# PS3604LR.net
KiCad netlist of a schematic drawn in Altium Designer
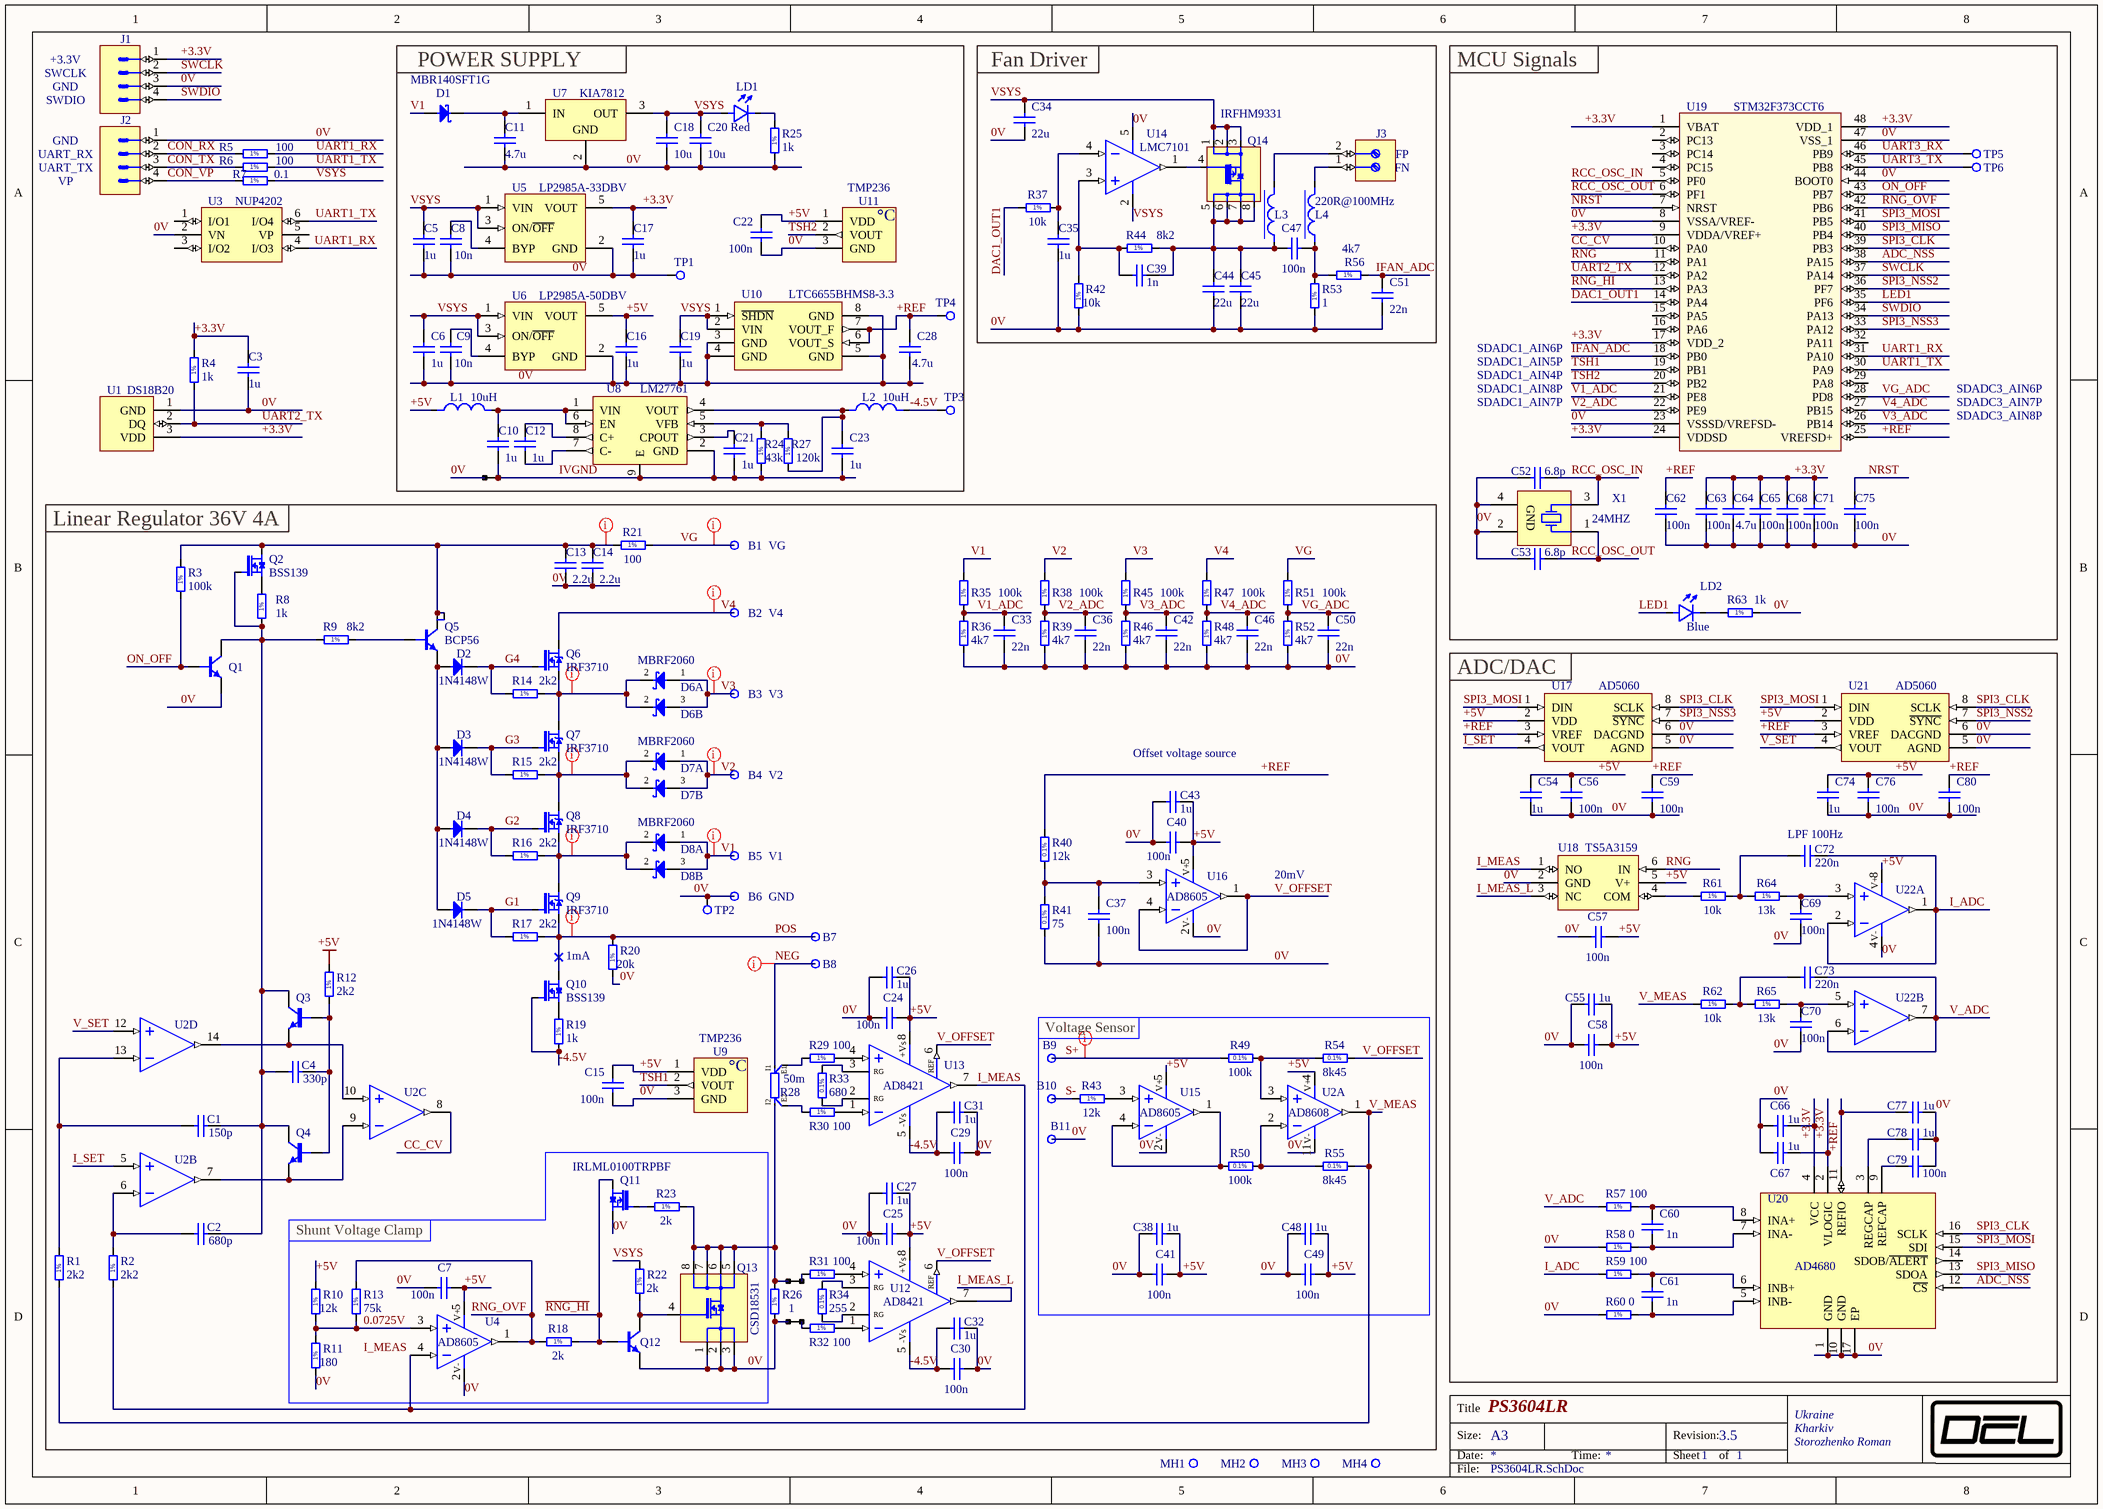
[diagram p0: PS3604LR.SchDoc]

(export (version "E")
  (design (tool "Eeschema 10.0.6"))
  (components
    (comp (ref "B1")
      (value "VG")
      (footprint "c250h130")
      (description "Single Terminal Socket")
      (fields (field (name "PART NUMBER") "PLATED_HOLE1.3_PAD2.5") (field (name "AUTHOR") "DEL"))
      (libsource (lib "Eletro-mechanical") (part "Single Terminal Socket"))
    )
    (comp (ref "B2")
      (value "V4")
      (footprint "c250h130")
      (description "Single Terminal Socket")
      (fields (field (name "PART NUMBER") "PLATED_HOLE1.3_PAD2.5") (field (name "AUTHOR") "DEL"))
      (libsource (lib "Eletro-mechanical") (part "Single Terminal Socket"))
    )
    (comp (ref "B3")
      (value "V3")
      (footprint "c250h130")
      (description "Single Terminal Socket")
      (fields (field (name "PART NUMBER") "PLATED_HOLE1.3_PAD2.5") (field (name "AUTHOR") "DEL"))
      (libsource (lib "Eletro-mechanical") (part "Single Terminal Socket"))
    )
    (comp (ref "B4")
      (value "V2")
      (footprint "c250h130")
      (description "Single Terminal Socket")
      (fields (field (name "PART NUMBER") "PLATED_HOLE1.3_PAD2.5") (field (name "AUTHOR") "DEL"))
      (libsource (lib "Eletro-mechanical") (part "Single Terminal Socket"))
    )
    (comp (ref "B5")
      (value "V1")
      (footprint "c250h130")
      (description "Single Terminal Socket")
      (fields (field (name "PART NUMBER") "PLATED_HOLE1.3_PAD2.5") (field (name "AUTHOR") "DEL"))
      (libsource (lib "Eletro-mechanical") (part "Single Terminal Socket"))
    )
    (comp (ref "B6")
      (value "GND")
      (footprint "c250h130")
      (description "Single Terminal Socket")
      (fields (field (name "PART NUMBER") "PLATED_HOLE1.3_PAD2.5") (field (name "AUTHOR") "DEL"))
      (libsource (lib "Eletro-mechanical") (part "Single Terminal Socket"))
    )
    (comp (ref "B7")
      (value "P")
      (footprint "c320h180")
      (description "Single Terminal Socket")
      (fields (field (name "PART NUMBER") "PLATED_HOLE1.8_PAD3.2") (field (name "AUTHOR") "DEL"))
      (libsource (lib "Eletro-mechanical") (part "Single Terminal Socket"))
    )
    (comp (ref "B8")
      (value "N")
      (footprint "c320h180")
      (description "Single Terminal Socket")
      (fields (field (name "PART NUMBER") "PLATED_HOLE1.8_PAD3.2") (field (name "AUTHOR") "DEL"))
      (libsource (lib "Eletro-mechanical") (part "Single Terminal Socket"))
    )
    (comp (ref "B9")
      (value "Plated Hole")
      (footprint "c150h100")
      (description "Single Terminal Socket")
      (fields (field (name "PART NUMBER") "PLATED_HOLE1.0_PAD1.5") (field (name "AUTHOR") "CERN DEM JLC"))
      (libsource (lib "Eletro-mechanical") (part "Single Terminal Socket"))
    )
    (comp (ref "B10")
      (value "Plated Hole")
      (footprint "c150h100")
      (description "Single Terminal Socket")
      (fields (field (name "PART NUMBER") "PLATED_HOLE1.0_PAD1.5") (field (name "AUTHOR") "CERN DEM JLC"))
      (libsource (lib "Eletro-mechanical") (part "Single Terminal Socket"))
    )
    (comp (ref "B11")
      (value "Plated Hole")
      (footprint "c150h100")
      (description "Single Terminal Socket")
      (fields (field (name "PART NUMBER") "PLATED_HOLE1.0_PAD1.5") (field (name "AUTHOR") "CERN DEM JLC"))
      (libsource (lib "Eletro-mechanical") (part "Single Terminal Socket"))
    )
    (comp (ref "C1")
      (value "150p")
      (footprint "CAPC2012X135N")
      (description "Non-polarised capacitor")
      (fields
        (field (name "PART NUMBER") "CC0805_150PF_50V_5%_NP0")
        (field (name "VOLTAGE") "50V")
        (field (name "AUTHOR") "CERN DEM JLC")
      )
      (libsource (lib "Capacitors") (part "Capacitor - non polarized"))
    )
    (comp (ref "C2")
      (value "680p")
      (footprint "CAPC2012X135N")
      (description "Non-polarised capacitor")
      (fields
        (field (name "PART NUMBER") "CC0805_680PF_50V_5%_NP0")
        (field (name "VOLTAGE") "50V")
        (field (name "AUTHOR") "CERN DEM JLC")
      )
      (libsource (lib "Capacitors") (part "Capacitor - non polarized"))
    )
    (comp (ref "C3")
      (value "1u")
      (footprint "CAPC1005X55N")
      (description "Non-polarised capacitor")
      (fields
        (field (name "PART NUMBER") "CC0402_1UF_10V_20%_X5R")
        (field (name "VOLTAGE") "10V")
        (field (name "AUTHOR") "ELMAN")
      )
      (libsource (lib "Capacitors") (part "Capacitor - non polarized"))
    )
    (comp (ref "C4")
      (value "330p")
      (footprint "CAPC2012X135N")
      (description "Non-polarised capacitor")
      (fields
        (field (name "PART NUMBER") "CC0805_330PF_50V_5%_NP0")
        (field (name "VOLTAGE") "50V")
        (field (name "AUTHOR") "CERN DEM JLC")
      )
      (libsource (lib "Capacitors") (part "Capacitor - non polarized"))
    )
    (comp (ref "C5")
      (value "1u")
      (footprint "CAPC1005X55N")
      (description "Non-polarised capacitor")
      (fields
        (field (name "PART NUMBER") "CC0402_1UF_10V_20%_X5R")
        (field (name "VOLTAGE") "10V")
        (field (name "AUTHOR") "ELMAN")
      )
      (libsource (lib "Capacitors") (part "Capacitor - non polarized"))
    )
    (comp (ref "C6")
      (value "1u")
      (footprint "CAPC1005X55N")
      (description "Non-polarised capacitor")
      (fields
        (field (name "PART NUMBER") "CC0402_1UF_10V_20%_X5R")
        (field (name "VOLTAGE") "10V")
        (field (name "AUTHOR") "ELMAN")
      )
      (libsource (lib "Capacitors") (part "Capacitor - non polarized"))
    )
    (comp (ref "C7")
      (value "100n")
      (footprint "CAPC1005X55N")
      (description "Non-polarised capacitor")
      (fields
        (field (name "PART NUMBER") "CC0402_100NF_50V_10%_X7R")
        (field (name "VOLTAGE") "50V")
        (field (name "AUTHOR") "DEL")
      )
      (libsource (lib "Capacitors") (part "Capacitor - non polarized"))
    )
    (comp (ref "C8")
      (value "10n")
      (footprint "CAPC1005X55N")
      (description "Non-polarised capacitor")
      (fields
        (field (name "PART NUMBER") "CC0402_10NF_50V_10%_X7R")
        (field (name "VOLTAGE") "50V")
        (field (name "AUTHOR") "DEL")
      )
      (libsource (lib "Capacitors") (part "Capacitor - non polarized"))
    )
    (comp (ref "C9")
      (value "10n")
      (footprint "CAPC1005X55N")
      (description "Non-polarised capacitor")
      (fields
        (field (name "PART NUMBER") "CC0402_10NF_50V_10%_X7R")
        (field (name "VOLTAGE") "50V")
        (field (name "AUTHOR") "DEL")
      )
      (libsource (lib "Capacitors") (part "Capacitor - non polarized"))
    )
    (comp (ref "C10")
      (value "1u")
      (footprint "CAPC1005X55N")
      (description "Non-polarised capacitor")
      (fields
        (field (name "PART NUMBER") "CC0402_1UF_10V_20%_X5R")
        (field (name "VOLTAGE") "10V")
        (field (name "AUTHOR") "ELMAN")
      )
      (libsource (lib "Capacitors") (part "Capacitor - non polarized"))
    )
    (comp (ref "C11")
      (value "4.7u")
      (footprint "CAPC3216X140N")
      (description "Non-polarised capacitor")
      (fields
        (field (name "PART NUMBER") "CC1206_4.7UF_50V_10%_X7R")
        (field (name "VOLTAGE") "50V")
        (field (name "AUTHOR") "DEL")
      )
      (libsource (lib "Capacitors") (part "Capacitor - non polarized"))
    )
    (comp (ref "C12")
      (value "1u")
      (footprint "CAPC1005X55N")
      (description "Non-polarised capacitor")
      (fields
        (field (name "PART NUMBER") "CC0402_1UF_10V_20%_X5R")
        (field (name "VOLTAGE") "10V")
        (field (name "AUTHOR") "ELMAN")
      )
      (libsource (lib "Capacitors") (part "Capacitor - non polarized"))
    )
    (comp (ref "C13")
      (value "2.2u")
      (footprint "CAPC3216X140N")
      (description "Non-polarised capacitor")
      (fields
        (field (name "PART NUMBER") "CC1206_2.2UF_100V_10%_X7R")
        (field (name "VOLTAGE") "100V")
        (field (name "AUTHOR") "DEL")
      )
      (libsource (lib "Capacitors") (part "Capacitor - non polarized"))
    )
    (comp (ref "C14")
      (value "2.2u")
      (footprint "CAPC3216X140N")
      (description "Non-polarised capacitor")
      (fields
        (field (name "PART NUMBER") "CC1206_2.2UF_100V_10%_X7R")
        (field (name "VOLTAGE") "100V")
        (field (name "AUTHOR") "DEL")
      )
      (libsource (lib "Capacitors") (part "Capacitor - non polarized"))
    )
    (comp (ref "C15")
      (value "100n")
      (footprint "CAPC1005X55N")
      (description "Non-polarised capacitor")
      (fields
        (field (name "PART NUMBER") "CC0402_100NF_50V_10%_X7R")
        (field (name "VOLTAGE") "50V")
        (field (name "AUTHOR") "DEL")
      )
      (libsource (lib "Capacitors") (part "Capacitor - non polarized"))
    )
    (comp (ref "C16")
      (value "1u")
      (footprint "CAPC1005X55N")
      (description "Non-polarised capacitor")
      (fields
        (field (name "PART NUMBER") "CC0402_1UF_10V_20%_X5R")
        (field (name "VOLTAGE") "10V")
        (field (name "AUTHOR") "ELMAN")
      )
      (libsource (lib "Capacitors") (part "Capacitor - non polarized"))
    )
    (comp (ref "C17")
      (value "1u")
      (footprint "CAPC1005X55N")
      (description "Non-polarised capacitor")
      (fields
        (field (name "PART NUMBER") "CC0402_1UF_10V_20%_X5R")
        (field (name "VOLTAGE") "10V")
        (field (name "AUTHOR") "ELMAN")
      )
      (libsource (lib "Capacitors") (part "Capacitor - non polarized"))
    )
    (comp (ref "C18")
      (value "10u")
      (footprint "CAPC3216X140N")
      (description "Non-polarised capacitor")
      (fields
        (field (name "PART NUMBER") "CC1206_10UF_16V_10%_X7R")
        (field (name "VOLTAGE") "16V")
        (field (name "AUTHOR") "CERN DEM JLC")
      )
      (libsource (lib "Capacitors") (part "Capacitor - non polarized"))
    )
    (comp (ref "C19")
      (value "1u")
      (footprint "CAPC1005X55N")
      (description "Non-polarised capacitor")
      (fields
        (field (name "PART NUMBER") "CC0402_1UF_10V_20%_X5R")
        (field (name "VOLTAGE") "10V")
        (field (name "AUTHOR") "ELMAN")
      )
      (libsource (lib "Capacitors") (part "Capacitor - non polarized"))
    )
    (comp (ref "C20")
      (value "10u")
      (footprint "CAPC3216X140N")
      (description "Non-polarised capacitor")
      (fields
        (field (name "PART NUMBER") "CC1206_10UF_16V_10%_X7R")
        (field (name "VOLTAGE") "16V")
        (field (name "AUTHOR") "CERN DEM JLC")
      )
      (libsource (lib "Capacitors") (part "Capacitor - non polarized"))
    )
    (comp (ref "C21")
      (value "1u")
      (footprint "CAPC1005X55N")
      (description "Non-polarised capacitor")
      (fields
        (field (name "PART NUMBER") "CC0402_1UF_10V_20%_X5R")
        (field (name "VOLTAGE") "10V")
        (field (name "AUTHOR") "ELMAN")
      )
      (libsource (lib "Capacitors") (part "Capacitor - non polarized"))
    )
    (comp (ref "C22")
      (value "100n")
      (footprint "CAPC1005X55N")
      (description "Non-polarised capacitor")
      (fields
        (field (name "PART NUMBER") "CC0402_100NF_50V_10%_X7R")
        (field (name "VOLTAGE") "50V")
        (field (name "AUTHOR") "DEL")
      )
      (libsource (lib "Capacitors") (part "Capacitor - non polarized"))
    )
    (comp (ref "C23")
      (value "1u")
      (footprint "CAPC1005X55N")
      (description "Non-polarised capacitor")
      (fields
        (field (name "PART NUMBER") "CC0402_1UF_10V_20%_X5R")
        (field (name "VOLTAGE") "10V")
        (field (name "AUTHOR") "ELMAN")
      )
      (libsource (lib "Capacitors") (part "Capacitor - non polarized"))
    )
    (comp (ref "C24")
      (value "100n")
      (footprint "CAPC1005X55N")
      (description "Non-polarised capacitor")
      (fields
        (field (name "PART NUMBER") "CC0402_100NF_50V_10%_X7R")
        (field (name "VOLTAGE") "50V")
        (field (name "AUTHOR") "DEL")
      )
      (libsource (lib "Capacitors") (part "Capacitor - non polarized"))
    )
    (comp (ref "C25")
      (value "100n")
      (footprint "CAPC1005X55N")
      (description "Non-polarised capacitor")
      (fields
        (field (name "PART NUMBER") "CC0402_100NF_50V_10%_X7R")
        (field (name "VOLTAGE") "50V")
        (field (name "AUTHOR") "DEL")
      )
      (libsource (lib "Capacitors") (part "Capacitor - non polarized"))
    )
    (comp (ref "C26")
      (value "1u")
      (footprint "CAPC1005X55N")
      (description "Non-polarised capacitor")
      (fields
        (field (name "PART NUMBER") "CC0402_1UF_10V_20%_X5R")
        (field (name "VOLTAGE") "10V")
        (field (name "AUTHOR") "ELMAN")
      )
      (libsource (lib "Capacitors") (part "Capacitor - non polarized"))
    )
    (comp (ref "C27")
      (value "1u")
      (footprint "CAPC1005X55N")
      (description "Non-polarised capacitor")
      (fields
        (field (name "PART NUMBER") "CC0402_1UF_10V_20%_X5R")
        (field (name "VOLTAGE") "10V")
        (field (name "AUTHOR") "ELMAN")
      )
      (libsource (lib "Capacitors") (part "Capacitor - non polarized"))
    )
    (comp (ref "C28")
      (value "4.7u")
      (footprint "CAPC1005X55N")
      (description "Non-polarised capacitor")
      (fields
        (field (name "PART NUMBER") "CC0402_4.7UF_10V_20%_X5R")
        (field (name "VOLTAGE") "10V")
        (field (name "AUTHOR") "DEL")
      )
      (libsource (lib "Capacitors") (part "Capacitor - non polarized"))
    )
    (comp (ref "C29")
      (value "100n")
      (footprint "CAPC1005X55N")
      (description "Non-polarised capacitor")
      (fields
        (field (name "PART NUMBER") "CC0402_100NF_50V_10%_X7R")
        (field (name "VOLTAGE") "50V")
        (field (name "AUTHOR") "DEL")
      )
      (libsource (lib "Capacitors") (part "Capacitor - non polarized"))
    )
    (comp (ref "C30")
      (value "100n")
      (footprint "CAPC1005X55N")
      (description "Non-polarised capacitor")
      (fields
        (field (name "PART NUMBER") "CC0402_100NF_50V_10%_X7R")
        (field (name "VOLTAGE") "50V")
        (field (name "AUTHOR") "DEL")
      )
      (libsource (lib "Capacitors") (part "Capacitor - non polarized"))
    )
    (comp (ref "C31")
      (value "1u")
      (footprint "CAPC1005X55N")
      (description "Non-polarised capacitor")
      (fields
        (field (name "PART NUMBER") "CC0402_1UF_10V_20%_X5R")
        (field (name "VOLTAGE") "10V")
        (field (name "AUTHOR") "ELMAN")
      )
      (libsource (lib "Capacitors") (part "Capacitor - non polarized"))
    )
    (comp (ref "C32")
      (value "1u")
      (footprint "CAPC1005X55N")
      (description "Non-polarised capacitor")
      (fields
        (field (name "PART NUMBER") "CC0402_1UF_10V_20%_X5R")
        (field (name "VOLTAGE") "10V")
        (field (name "AUTHOR") "ELMAN")
      )
      (libsource (lib "Capacitors") (part "Capacitor - non polarized"))
    )
    (comp (ref "C33")
      (value "22n")
      (footprint "CAPC1005X55N")
      (description "Non-polarised capacitor")
      (fields
        (field (name "PART NUMBER") "CC0402_22NF_16V_10%_X7R")
        (field (name "VOLTAGE") "16V")
        (field (name "AUTHOR") "CERN DEM JLC")
      )
      (libsource (lib "Capacitors") (part "Capacitor - non polarized"))
    )
    (comp (ref "C34")
      (value "22u")
      (footprint "CAPC3216X100N")
      (description "Non-polarised capacitor")
      (fields
        (field (name "PART NUMBER") "CC1206_22UF_16V_20%_X5R")
        (field (name "VOLTAGE") "16V")
        (field (name "AUTHOR") "D_EL")
      )
      (libsource (lib "Capacitors") (part "Capacitor - non polarized"))
    )
    (comp (ref "C35")
      (value "1u")
      (footprint "CAPC1005X55N")
      (description "Non-polarised capacitor")
      (fields
        (field (name "PART NUMBER") "CC0402_1UF_10V_20%_X5R")
        (field (name "VOLTAGE") "10V")
        (field (name "AUTHOR") "ELMAN")
      )
      (libsource (lib "Capacitors") (part "Capacitor - non polarized"))
    )
    (comp (ref "C36")
      (value "22n")
      (footprint "CAPC1005X55N")
      (description "Non-polarised capacitor")
      (fields
        (field (name "PART NUMBER") "CC0402_22NF_16V_10%_X7R")
        (field (name "VOLTAGE") "16V")
        (field (name "AUTHOR") "CERN DEM JLC")
      )
      (libsource (lib "Capacitors") (part "Capacitor - non polarized"))
    )
    (comp (ref "C37")
      (value "100n")
      (footprint "CAPC1005X55N")
      (description "Non-polarised capacitor")
      (fields
        (field (name "PART NUMBER") "CC0402_100NF_50V_10%_X7R")
        (field (name "VOLTAGE") "50V")
        (field (name "AUTHOR") "DEL")
      )
      (libsource (lib "Capacitors") (part "Capacitor - non polarized"))
    )
    (comp (ref "C38")
      (value "1u")
      (footprint "CAPC1005X55N")
      (description "Non-polarised capacitor")
      (fields
        (field (name "PART NUMBER") "CC0402_1UF_10V_20%_X5R")
        (field (name "VOLTAGE") "10V")
        (field (name "AUTHOR") "ELMAN")
      )
      (libsource (lib "Capacitors") (part "Capacitor - non polarized"))
    )
    (comp (ref "C39")
      (value "1n")
      (footprint "CAPC1005X55N")
      (description "Non-polarised capacitor")
      (fields
        (field (name "PART NUMBER") "CC0402_1NF_50V_5%_NP0")
        (field (name "VOLTAGE") "50V")
        (field (name "AUTHOR") "ROMAN")
      )
      (libsource (lib "Capacitors") (part "Capacitor - non polarized"))
    )
    (comp (ref "C40")
      (value "100n")
      (footprint "CAPC1005X55N")
      (description "Non-polarised capacitor")
      (fields
        (field (name "PART NUMBER") "CC0402_100NF_50V_10%_X7R")
        (field (name "VOLTAGE") "50V")
        (field (name "AUTHOR") "DEL")
      )
      (libsource (lib "Capacitors") (part "Capacitor - non polarized"))
    )
    (comp (ref "C41")
      (value "100n")
      (footprint "CAPC1005X55N")
      (description "Non-polarised capacitor")
      (fields
        (field (name "PART NUMBER") "CC0402_100NF_50V_10%_X7R")
        (field (name "VOLTAGE") "50V")
        (field (name "AUTHOR") "DEL")
      )
      (libsource (lib "Capacitors") (part "Capacitor - non polarized"))
    )
    (comp (ref "C42")
      (value "22n")
      (footprint "CAPC1005X55N")
      (description "Non-polarised capacitor")
      (fields
        (field (name "PART NUMBER") "CC0402_22NF_16V_10%_X7R")
        (field (name "VOLTAGE") "16V")
        (field (name "AUTHOR") "CERN DEM JLC")
      )
      (libsource (lib "Capacitors") (part "Capacitor - non polarized"))
    )
    (comp (ref "C43")
      (value "1u")
      (footprint "CAPC1005X55N")
      (description "Non-polarised capacitor")
      (fields
        (field (name "PART NUMBER") "CC0402_1UF_10V_20%_X5R")
        (field (name "VOLTAGE") "10V")
        (field (name "AUTHOR") "ELMAN")
      )
      (libsource (lib "Capacitors") (part "Capacitor - non polarized"))
    )
    (comp (ref "C44")
      (value "22u")
      (footprint "CAPC3216X100N")
      (description "Non-polarised capacitor")
      (fields
        (field (name "PART NUMBER") "CC1206_22UF_16V_20%_X5R")
        (field (name "VOLTAGE") "16V")
        (field (name "AUTHOR") "D_EL")
      )
      (libsource (lib "Capacitors") (part "Capacitor - non polarized"))
    )
    (comp (ref "C45")
      (value "22u")
      (footprint "CAPC3216X100N")
      (description "Non-polarised capacitor")
      (fields
        (field (name "PART NUMBER") "CC1206_22UF_16V_20%_X5R")
        (field (name "VOLTAGE") "16V")
        (field (name "AUTHOR") "D_EL")
      )
      (libsource (lib "Capacitors") (part "Capacitor - non polarized"))
    )
    (comp (ref "C46")
      (value "22n")
      (footprint "CAPC1005X55N")
      (description "Non-polarised capacitor")
      (fields
        (field (name "PART NUMBER") "CC0402_22NF_16V_10%_X7R")
        (field (name "VOLTAGE") "16V")
        (field (name "AUTHOR") "CERN DEM JLC")
      )
      (libsource (lib "Capacitors") (part "Capacitor - non polarized"))
    )
    (comp (ref "C47")
      (value "100n")
      (footprint "CAPC1005X55N")
      (description "Non-polarised capacitor")
      (fields
        (field (name "PART NUMBER") "CC0402_100NF_50V_10%_X7R")
        (field (name "VOLTAGE") "50V")
        (field (name "AUTHOR") "DEL")
      )
      (libsource (lib "Capacitors") (part "Capacitor - non polarized"))
    )
    (comp (ref "C48")
      (value "1u")
      (footprint "CAPC1005X55N")
      (description "Non-polarised capacitor")
      (fields
        (field (name "PART NUMBER") "CC0402_1UF_10V_20%_X5R")
        (field (name "VOLTAGE") "10V")
        (field (name "AUTHOR") "ELMAN")
      )
      (libsource (lib "Capacitors") (part "Capacitor - non polarized"))
    )
    (comp (ref "C49")
      (value "100n")
      (footprint "CAPC1005X55N")
      (description "Non-polarised capacitor")
      (fields
        (field (name "PART NUMBER") "CC0402_100NF_50V_10%_X7R")
        (field (name "VOLTAGE") "50V")
        (field (name "AUTHOR") "DEL")
      )
      (libsource (lib "Capacitors") (part "Capacitor - non polarized"))
    )
    (comp (ref "C50")
      (value "22n")
      (footprint "CAPC1005X55N")
      (description "Non-polarised capacitor")
      (fields
        (field (name "PART NUMBER") "CC0402_22NF_16V_10%_X7R")
        (field (name "VOLTAGE") "16V")
        (field (name "AUTHOR") "CERN DEM JLC")
      )
      (libsource (lib "Capacitors") (part "Capacitor - non polarized"))
    )
    (comp (ref "C51")
      (value "22n")
      (footprint "CAPC1005X55N")
      (description "Non-polarised capacitor")
      (fields
        (field (name "PART NUMBER") "CC0402_22NF_16V_10%_X7R")
        (field (name "VOLTAGE") "16V")
        (field (name "AUTHOR") "CERN DEM JLC")
      )
      (libsource (lib "Capacitors") (part "Capacitor - non polarized"))
    )
    (comp (ref "C52")
      (value "6.8p")
      (footprint "CAPC1005X55N")
      (description "Non-polarised capacitor")
      (fields
        (field (name "PART NUMBER") "CC0402_6.8PF_50V_0.5PF_NP0")
        (field (name "VOLTAGE") "50V")
        (field (name "AUTHOR") "CERN DEM JLC")
      )
      (libsource (lib "Capacitors") (part "Capacitor - non polarized"))
    )
    (comp (ref "C53")
      (value "6.8p")
      (footprint "CAPC1005X55N")
      (description "Non-polarised capacitor")
      (fields
        (field (name "PART NUMBER") "CC0402_6.8PF_50V_0.5PF_NP0")
        (field (name "VOLTAGE") "50V")
        (field (name "AUTHOR") "CERN DEM JLC")
      )
      (libsource (lib "Capacitors") (part "Capacitor - non polarized"))
    )
    (comp (ref "C54")
      (value "1u")
      (footprint "CAPC1005X55N")
      (description "Non-polarised capacitor")
      (fields
        (field (name "PART NUMBER") "CC0402_1UF_10V_20%_X5R")
        (field (name "VOLTAGE") "10V")
        (field (name "AUTHOR") "ELMAN")
      )
      (libsource (lib "Capacitors") (part "Capacitor - non polarized"))
    )
    (comp (ref "C55")
      (value "1u")
      (footprint "CAPC1005X55N")
      (description "Non-polarised capacitor")
      (fields
        (field (name "PART NUMBER") "CC0402_1UF_10V_20%_X5R")
        (field (name "VOLTAGE") "10V")
        (field (name "AUTHOR") "ELMAN")
      )
      (libsource (lib "Capacitors") (part "Capacitor - non polarized"))
    )
    (comp (ref "C56")
      (value "100n")
      (footprint "CAPC1005X55N")
      (description "Non-polarised capacitor")
      (fields
        (field (name "PART NUMBER") "CC0402_100NF_50V_10%_X7R")
        (field (name "VOLTAGE") "50V")
        (field (name "AUTHOR") "DEL")
      )
      (libsource (lib "Capacitors") (part "Capacitor - non polarized"))
    )
    (comp (ref "C57")
      (value "100n")
      (footprint "CAPC1005X55N")
      (description "Non-polarised capacitor")
      (fields
        (field (name "PART NUMBER") "CC0402_100NF_50V_10%_X7R")
        (field (name "VOLTAGE") "50V")
        (field (name "AUTHOR") "DEL")
      )
      (libsource (lib "Capacitors") (part "Capacitor - non polarized"))
    )
    (comp (ref "C58")
      (value "100n")
      (footprint "CAPC1005X55N")
      (description "Non-polarised capacitor")
      (fields
        (field (name "PART NUMBER") "CC0402_100NF_50V_10%_X7R")
        (field (name "VOLTAGE") "50V")
        (field (name "AUTHOR") "DEL")
      )
      (libsource (lib "Capacitors") (part "Capacitor - non polarized"))
    )
    (comp (ref "C59")
      (value "100n")
      (footprint "CAPC1005X55N")
      (description "Non-polarised capacitor")
      (fields
        (field (name "PART NUMBER") "CC0402_100NF_50V_10%_X7R")
        (field (name "VOLTAGE") "50V")
        (field (name "AUTHOR") "DEL")
      )
      (libsource (lib "Capacitors") (part "Capacitor - non polarized"))
    )
    (comp (ref "C60")
      (value "1n")
      (footprint "CAPC1005X55N")
      (description "Non-polarised capacitor")
      (fields
        (field (name "PART NUMBER") "CC0402_1NF_50V_5%_NP0")
        (field (name "VOLTAGE") "50V")
        (field (name "AUTHOR") "ROMAN")
      )
      (libsource (lib "Capacitors") (part "Capacitor - non polarized"))
    )
    (comp (ref "C61")
      (value "1n")
      (footprint "CAPC1005X55N")
      (description "Non-polarised capacitor")
      (fields
        (field (name "PART NUMBER") "CC0402_1NF_50V_5%_NP0")
        (field (name "VOLTAGE") "50V")
        (field (name "AUTHOR") "ROMAN")
      )
      (libsource (lib "Capacitors") (part "Capacitor - non polarized"))
    )
    (comp (ref "C62")
      (value "100n")
      (footprint "CAPC1005X55N")
      (description "Non-polarised capacitor")
      (fields
        (field (name "PART NUMBER") "CC0402_100NF_50V_10%_X7R")
        (field (name "VOLTAGE") "50V")
        (field (name "AUTHOR") "DEL")
      )
      (libsource (lib "Capacitors") (part "Capacitor - non polarized"))
    )
    (comp (ref "C63")
      (value "100n")
      (footprint "CAPC1005X55N")
      (description "Non-polarised capacitor")
      (fields
        (field (name "PART NUMBER") "CC0402_100NF_50V_10%_X7R")
        (field (name "VOLTAGE") "50V")
        (field (name "AUTHOR") "DEL")
      )
      (libsource (lib "Capacitors") (part "Capacitor - non polarized"))
    )
    (comp (ref "C64")
      (value "4.7u")
      (footprint "CAPC1005X55N")
      (description "Non-polarised capacitor")
      (fields
        (field (name "PART NUMBER") "CC0402_4.7UF_10V_20%_X5R")
        (field (name "VOLTAGE") "10V")
        (field (name "AUTHOR") "DEL")
      )
      (libsource (lib "Capacitors") (part "Capacitor - non polarized"))
    )
    (comp (ref "C65")
      (value "100n")
      (footprint "CAPC1005X55N")
      (description "Non-polarised capacitor")
      (fields
        (field (name "PART NUMBER") "CC0402_100NF_50V_10%_X7R")
        (field (name "VOLTAGE") "50V")
        (field (name "AUTHOR") "DEL")
      )
      (libsource (lib "Capacitors") (part "Capacitor - non polarized"))
    )
    (comp (ref "C66")
      (value "1u")
      (footprint "CAPC1005X55N")
      (description "Non-polarised capacitor")
      (fields
        (field (name "PART NUMBER") "CC0402_1UF_10V_20%_X5R")
        (field (name "VOLTAGE") "10V")
        (field (name "AUTHOR") "ELMAN")
      )
      (libsource (lib "Capacitors") (part "Capacitor - non polarized"))
    )
    (comp (ref "C67")
      (value "1u")
      (footprint "CAPC1005X55N")
      (description "Non-polarised capacitor")
      (fields
        (field (name "PART NUMBER") "CC0402_1UF_10V_20%_X5R")
        (field (name "VOLTAGE") "10V")
        (field (name "AUTHOR") "ELMAN")
      )
      (libsource (lib "Capacitors") (part "Capacitor - non polarized"))
    )
    (comp (ref "C68")
      (value "100n")
      (footprint "CAPC1005X55N")
      (description "Non-polarised capacitor")
      (fields
        (field (name "PART NUMBER") "CC0402_100NF_50V_10%_X7R")
        (field (name "VOLTAGE") "50V")
        (field (name "AUTHOR") "DEL")
      )
      (libsource (lib "Capacitors") (part "Capacitor - non polarized"))
    )
    (comp (ref "C69")
      (value "100n")
      (footprint "CAPC1005X55N")
      (description "Non-polarised capacitor")
      (fields
        (field (name "PART NUMBER") "CC0402_100NF_50V_10%_X7R")
        (field (name "VOLTAGE") "50V")
        (field (name "AUTHOR") "DEL")
      )
      (libsource (lib "Capacitors") (part "Capacitor - non polarized"))
    )
    (comp (ref "C70")
      (value "100n")
      (footprint "CAPC1005X55N")
      (description "Non-polarised capacitor")
      (fields
        (field (name "PART NUMBER") "CC0402_100NF_50V_10%_X7R")
        (field (name "VOLTAGE") "50V")
        (field (name "AUTHOR") "DEL")
      )
      (libsource (lib "Capacitors") (part "Capacitor - non polarized"))
    )
    (comp (ref "C71")
      (value "100n")
      (footprint "CAPC1005X55N")
      (description "Non-polarised capacitor")
      (fields
        (field (name "PART NUMBER") "CC0402_100NF_50V_10%_X7R")
        (field (name "VOLTAGE") "50V")
        (field (name "AUTHOR") "DEL")
      )
      (libsource (lib "Capacitors") (part "Capacitor - non polarized"))
    )
    (comp (ref "C72")
      (value "220n")
      (footprint "CAPC1005X55N")
      (description "Non-polarised capacitor")
      (fields
        (field (name "PART NUMBER") "CC0402_220NF_6.3V_10%_X5R")
        (field (name "VOLTAGE") "6.3V")
        (field (name "AUTHOR") "CERN DEM JLC")
      )
      (libsource (lib "Capacitors") (part "Capacitor - non polarized"))
    )
    (comp (ref "C73")
      (value "220n")
      (footprint "CAPC1005X55N")
      (description "Non-polarised capacitor")
      (fields
        (field (name "PART NUMBER") "CC0402_220NF_6.3V_10%_X5R")
        (field (name "VOLTAGE") "6.3V")
        (field (name "AUTHOR") "CERN DEM JLC")
      )
      (libsource (lib "Capacitors") (part "Capacitor - non polarized"))
    )
    (comp (ref "C74")
      (value "1u")
      (footprint "CAPC1005X55N")
      (description "Non-polarised capacitor")
      (fields
        (field (name "PART NUMBER") "CC0402_1UF_10V_20%_X5R")
        (field (name "VOLTAGE") "10V")
        (field (name "AUTHOR") "ELMAN")
      )
      (libsource (lib "Capacitors") (part "Capacitor - non polarized"))
    )
    (comp (ref "C75")
      (value "100n")
      (footprint "CAPC1005X55N")
      (description "Non-polarised capacitor")
      (fields
        (field (name "PART NUMBER") "CC0402_100NF_50V_10%_X7R")
        (field (name "VOLTAGE") "50V")
        (field (name "AUTHOR") "DEL")
      )
      (libsource (lib "Capacitors") (part "Capacitor - non polarized"))
    )
    (comp (ref "C76")
      (value "100n")
      (footprint "CAPC1005X55N")
      (description "Non-polarised capacitor")
      (fields
        (field (name "PART NUMBER") "CC0402_100NF_50V_10%_X7R")
        (field (name "VOLTAGE") "50V")
        (field (name "AUTHOR") "DEL")
      )
      (libsource (lib "Capacitors") (part "Capacitor - non polarized"))
    )
    (comp (ref "C77")
      (value "1u")
      (footprint "CAPC1005X55N")
      (description "Non-polarised capacitor")
      (fields
        (field (name "PART NUMBER") "CC0402_1UF_10V_20%_X5R")
        (field (name "VOLTAGE") "10V")
        (field (name "AUTHOR") "ELMAN")
      )
      (libsource (lib "Capacitors") (part "Capacitor - non polarized"))
    )
    (comp (ref "C78")
      (value "1u")
      (footprint "CAPC1005X55N")
      (description "Non-polarised capacitor")
      (fields
        (field (name "PART NUMBER") "CC0402_1UF_10V_20%_X5R")
        (field (name "VOLTAGE") "10V")
        (field (name "AUTHOR") "ELMAN")
      )
      (libsource (lib "Capacitors") (part "Capacitor - non polarized"))
    )
    (comp (ref "C79")
      (value "100n")
      (footprint "CAPC1005X55N")
      (description "Non-polarised capacitor")
      (fields
        (field (name "PART NUMBER") "CC0402_100NF_50V_10%_X7R")
        (field (name "VOLTAGE") "50V")
        (field (name "AUTHOR") "DEL")
      )
      (libsource (lib "Capacitors") (part "Capacitor - non polarized"))
    )
    (comp (ref "C80")
      (value "100n")
      (footprint "CAPC1005X55N")
      (description "Non-polarised capacitor")
      (fields
        (field (name "PART NUMBER") "CC0402_100NF_50V_10%_X7R")
        (field (name "VOLTAGE") "50V")
        (field (name "AUTHOR") "DEL")
      )
      (libsource (lib "Capacitors") (part "Capacitor - non polarized"))
    )
    (comp (ref "D1")
      (value "MBR140SFT1G")
      (footprint "SOD-123FL")
      (description "Schottky Diode")
      (fields
        (field (name "VOLTAGE") "40V")
        (field (name "POWER") "1A")
        (field (name "AUTHOR") "CERN DEM JLC")
      )
      (libsource (lib "ICs And Semiconductors") (part "Diode Schottky"))
    )
    (comp (ref "D2")
      (value "1N4148W")
      (footprint "SOD3715X145N")
      (description "Diode")
      (fields (field (name "VOLTAGE") "75V") (field (name "POWER") "150mA") (field (name "AUTHOR") "DEL"))
      (libsource (lib "ICs And Semiconductors") (part "Diode"))
    )
    (comp (ref "D3")
      (value "1N4148W")
      (footprint "SOD3715X145N")
      (description "Diode")
      (fields (field (name "VOLTAGE") "75V") (field (name "POWER") "150mA") (field (name "AUTHOR") "DEL"))
      (libsource (lib "ICs And Semiconductors") (part "Diode"))
    )
    (comp (ref "D4")
      (value "1N4148W")
      (footprint "SOD3715X145N")
      (description "Diode")
      (fields (field (name "VOLTAGE") "75V") (field (name "POWER") "150mA") (field (name "AUTHOR") "DEL"))
      (libsource (lib "ICs And Semiconductors") (part "Diode"))
    )
    (comp (ref "D5")
      (value "1N4148W")
      (footprint "SOD3715X145N")
      (description "Diode")
      (fields (field (name "VOLTAGE") "75V") (field (name "POWER") "150mA") (field (name "AUTHOR") "DEL"))
      (libsource (lib "ICs And Semiconductors") (part "Diode"))
    )
    (comp (ref "D6")
      (value "MBRF2060")
      (footprint "TO-220-H-OUTSIDE")
      (description "Dual Common Cathode Schottky Diodes")
      (fields
        (field (name "PART NUMBER") "MBRF2060CTG_h_outside")
        (field (name "VOLTAGE") "60V")
        (field (name "AUTHOR") "DEL")
      )
      (libsource (lib "ICs And Semiconductors") (part "Diode Schottky x2 A1C2_A3C2"))
    )
    (comp (ref "D7")
      (value "MBRF2060")
      (footprint "TO-220-H-OUTSIDE")
      (description "Dual Common Cathode Schottky Diodes")
      (fields
        (field (name "PART NUMBER") "MBRF2060CTG_h_outside")
        (field (name "VOLTAGE") "60V")
        (field (name "AUTHOR") "DEL")
      )
      (libsource (lib "ICs And Semiconductors") (part "Diode Schottky x2 A1C2_A3C2"))
    )
    (comp (ref "D8")
      (value "MBRF2060")
      (footprint "TO-220-H-OUTSIDE")
      (description "Dual Common Cathode Schottky Diodes")
      (fields
        (field (name "PART NUMBER") "MBRF2060CTG_h_outside")
        (field (name "VOLTAGE") "60V")
        (field (name "AUTHOR") "DEL")
      )
      (libsource (lib "ICs And Semiconductors") (part "Diode Schottky x2 A1C2_A3C2"))
    )
    (comp (ref "J1")
      (value "Header 4")
      (footprint "3M_929550-0104-EU")
      (description "Connector 4 Male")
      (fields
        (field (name "PART NUMBER") "3M_929550-0104-EU")
        (field (name "MANUFACTURER") "3M")
        (field (name "AUTHOR") "DEL")
      )
      (libsource (lib "Connectors") (part "Connector 4 Male"))
    )
    (comp (ref "J2")
      (value "SPOX")
      (footprint "MOLEX_22-03-5045")
      (description "Connector 4 Male")
      (fields
        (field (name "PART NUMBER") "MOLEX_22-03-5045")
        (field (name "MANUFACTURER") "MOLEX")
        (field (name "AUTHOR") "DEL")
      )
      (libsource (lib "Connectors") (part "Connector 4 Male"))
    )
    (comp (ref "J3")
      (value "~")
      (footprint "PHOENIX_1725656")
      (description "Terminal Block, 2 Positions, Screw Connection")
      (fields
        (field (name "PART NUMBER") "PHOENIX_1725656")
        (field (name "MANUFACTURER") "PHOENIX CONTACT")
        (field (name "AUTHOR") "CERN DEM JMW")
      )
      (libsource (lib "Connectors") (part "Terminal Block_2 Positions_Screw Connection"))
    )
    (comp (ref "L1")
      (value "10uH")
      (footprint "INDC1608X95N")
      (description "Inductor")
      (fields
        (field (name "PART NUMBER") "IND0603_10UH_MURATA_LQM18FN100M00D")
        (field (name "POWER") "50mA")
        (field (name "AUTHOR") "DEL")
      )
      (libsource (lib "Inductors & Transformers") (part "Inductor"))
    )
    (comp (ref "L2")
      (value "10uH")
      (footprint "INDC1608X95N")
      (description "Inductor")
      (fields
        (field (name "PART NUMBER") "IND0603_10UH_MURATA_LQM18FN100M00D")
        (field (name "POWER") "50mA")
        (field (name "AUTHOR") "DEL")
      )
      (libsource (lib "Inductors & Transformers") (part "Inductor"))
    )
    (comp (ref "L3")
      (value "220R@100MHz")
      (footprint "INDC1608X95N")
      (description "Inductor With Magnetic core")
      (fields
        (field (name "PART NUMBER") "FB0603_SAMSUNG_CIS10P221NC")
        (field (name "POWER") "2.5A")
        (field (name "AUTHOR") "ELMAN")
      )
      (libsource (lib "Inductors & Transformers") (part "Inductor With Magnetic core"))
    )
    (comp (ref "L4")
      (value "220R@100MHz")
      (footprint "INDC1608X95N")
      (description "Inductor With Magnetic core")
      (fields
        (field (name "PART NUMBER") "FB0603_SAMSUNG_CIS10P221NC")
        (field (name "POWER") "2.5A")
        (field (name "AUTHOR") "ELMAN")
      )
      (libsource (lib "Inductors & Transformers") (part "Inductor With Magnetic core"))
    )
    (comp (ref "LD1")
      (value "Red")
      (footprint "LEDC1608X80N_RED")
      (description "LED 1C 2A")
      (fields
        (field (name "PART NUMBER") "LED_OF-SMD1608R")
        (field (name "MANUFACTURER") "OPTOFLASH")
        (field (name "AUTHOR") "ELMAN")
      )
      (libsource (lib "ICs And Semiconductors") (part "LED 1C 2A"))
    )
    (comp (ref "LD2")
      (value "Blue")
      (footprint "LEDC1608X80N_BLUE")
      (description "LED 1C 2A")
      (fields
        (field (name "PART NUMBER") "LED_OF-SMD1608B")
        (field (name "MANUFACTURER") "OPTOFLASH")
        (field (name "AUTHOR") "DEL")
      )
      (libsource (lib "ICs And Semiconductors") (part "LED 1C 2A"))
    )
    (comp (ref "MH1")
      (value "Non Plated Hole")
      (footprint "MTG600H320V8P")
      (description "Single Terminal Socket")
      (fields (field (name "PART NUMBER") "NON-PLATED_HOLE3.2_PAD6.0_8p") (field (name "AUTHOR") "DEL"))
      (libsource (lib "Eletro-mechanical") (part "Single Terminal Socket"))
    )
    (comp (ref "MH2")
      (value "Non Plated Hole")
      (footprint "MTG600H320V8P")
      (description "Single Terminal Socket")
      (fields (field (name "PART NUMBER") "NON-PLATED_HOLE3.2_PAD6.0_8p") (field (name "AUTHOR") "DEL"))
      (libsource (lib "Eletro-mechanical") (part "Single Terminal Socket"))
    )
    (comp (ref "MH3")
      (value "Non Plated Hole")
      (footprint "MTG600H320V8P")
      (description "Single Terminal Socket")
      (fields (field (name "PART NUMBER") "NON-PLATED_HOLE3.2_PAD6.0_8p") (field (name "AUTHOR") "DEL"))
      (libsource (lib "Eletro-mechanical") (part "Single Terminal Socket"))
    )
    (comp (ref "MH4")
      (value "Non Plated Hole")
      (footprint "MTG600H320V8P")
      (description "Single Terminal Socket")
      (fields (field (name "PART NUMBER") "NON-PLATED_HOLE3.2_PAD6.0_8p") (field (name "AUTHOR") "DEL"))
      (libsource (lib "Eletro-mechanical") (part "Single Terminal Socket"))
    )
    (comp (ref "n1")
      (value "Net Tie")
      (footprint "NetTie_025_04")
      (fields (field (name "PART NUMBER") "NET_TIE_0.25_0.4") (field (name "AUTHOR") "DEL"))
      (libsource (lib "Eletro-mechanical") (part "Net Tie"))
    )
    (comp (ref "n2")
      (value "Net Tie")
      (footprint "NetTie_025_04")
      (fields (field (name "PART NUMBER") "NET_TIE_0.25_0.4") (field (name "AUTHOR") "DEL"))
      (libsource (lib "Eletro-mechanical") (part "Net Tie"))
    )
    (comp (ref "n3")
      (value "Net Tie")
      (footprint "NetTie_025_04")
      (fields (field (name "PART NUMBER") "NET_TIE_0.25_0.4") (field (name "AUTHOR") "DEL"))
      (libsource (lib "Eletro-mechanical") (part "Net Tie"))
    )
    (comp (ref "Q1")
      (value "MMBT5551")
      (footprint "SOT95P240X130-3N")
      (description "NPN Transistor")
      (fields
        (field (name "PART NUMBER") "MMBT5551L")
        (field (name "MANUFACTURER") "ON SEMICONDICTOR")
        (field (name "AUTHOR") "DEL")
      )
      (libsource (lib "ICs And Semiconductors") (part "NPN B1 E2 C3"))
    )
    (comp (ref "Q2")
      (value "BSS139")
      (footprint "SOT95P240X110-3N")
      (description "N-CHANNEL MOSFET Depletion-mode WITH DIODE")
      (fields
        (field (name "MANUFACTURER") "INFINEON")
        (field (name "MANUFACTURER PART NUMBER") "BSS139H6327XTSA1")
        (field (name "AUTHOR") "D_EL")
      )
      (libsource (lib "ICs And Semiconductors") (part "N-MOSFET-DEPLETION-D 1G 2S 3D"))
    )
    (comp (ref "Q3")
      (value "MMBT5551")
      (footprint "SOT95P240X130-3N")
      (description "NPN Transistor")
      (fields
        (field (name "PART NUMBER") "MMBT5551L")
        (field (name "MANUFACTURER") "ON SEMICONDICTOR")
        (field (name "AUTHOR") "DEL")
      )
      (libsource (lib "ICs And Semiconductors") (part "NPN B1 E2 C3"))
    )
    (comp (ref "Q4")
      (value "MMBT5551")
      (footprint "SOT95P240X130-3N")
      (description "NPN Transistor")
      (fields
        (field (name "PART NUMBER") "MMBT5551L")
        (field (name "MANUFACTURER") "ON SEMICONDICTOR")
        (field (name "AUTHOR") "DEL")
      )
      (libsource (lib "ICs And Semiconductors") (part "NPN B1 E2 C3"))
    )
    (comp (ref "Q5")
      (value "BCP56")
      (footprint "SOT230P700X180-4N")
      (description "NPN Transistor")
      (fields (field (name "MANUFACTURER") "NXP SEMICONDUCTORS") (field (name "AUTHOR") "DEL"))
      (libsource (lib "ICs And Semiconductors") (part "NPN B1 C2 E3 C4"))
    )
    (comp (ref "Q6")
      (value "IRF3710")
      (footprint "TO-220-H-OUTSIDE")
      (description "N-CHANNEL MOSFET WITH ZENER DIODE")
      (fields
        (field (name "PART NUMBER") "IRF3710_h_outside")
        (field (name "MANUFACTURER") "INTERNATIONAL RECTIFIER")
        (field (name "AUTHOR") "DEL")
      )
      (libsource (lib "ICs And Semiconductors") (part "N-MOSFET-DZ 1G 2D 3S"))
    )
    (comp (ref "Q7")
      (value "IRF3710")
      (footprint "TO-220-H-OUTSIDE")
      (description "N-CHANNEL MOSFET WITH ZENER DIODE")
      (fields
        (field (name "PART NUMBER") "IRF3710_h_outside")
        (field (name "MANUFACTURER") "INTERNATIONAL RECTIFIER")
        (field (name "AUTHOR") "DEL")
      )
      (libsource (lib "ICs And Semiconductors") (part "N-MOSFET-DZ 1G 2D 3S"))
    )
    (comp (ref "Q8")
      (value "IRF3710")
      (footprint "TO-220-H-OUTSIDE")
      (description "N-CHANNEL MOSFET WITH ZENER DIODE")
      (fields
        (field (name "PART NUMBER") "IRF3710_h_outside")
        (field (name "MANUFACTURER") "INTERNATIONAL RECTIFIER")
        (field (name "AUTHOR") "DEL")
      )
      (libsource (lib "ICs And Semiconductors") (part "N-MOSFET-DZ 1G 2D 3S"))
    )
    (comp (ref "Q9")
      (value "IRF3710")
      (footprint "TO-220-H-OUTSIDE")
      (description "N-CHANNEL MOSFET WITH ZENER DIODE")
      (fields
        (field (name "PART NUMBER") "IRF3710_h_outside")
        (field (name "MANUFACTURER") "INTERNATIONAL RECTIFIER")
        (field (name "AUTHOR") "DEL")
      )
      (libsource (lib "ICs And Semiconductors") (part "N-MOSFET-DZ 1G 2D 3S"))
    )
    (comp (ref "Q10")
      (value "BSS139")
      (footprint "SOT95P240X110-3N")
      (description "N-CHANNEL MOSFET Depletion-mode WITH DIODE")
      (fields
        (field (name "MANUFACTURER") "INFINEON")
        (field (name "MANUFACTURER PART NUMBER") "BSS139H6327XTSA1")
        (field (name "AUTHOR") "D_EL")
      )
      (libsource (lib "ICs And Semiconductors") (part "N-MOSFET-DEPLETION-D 1G 2S 3D"))
    )
    (comp (ref "Q11")
      (value "IRLML0100TRPBF")
      (footprint "SOT95P237X112-3N")
      (description "N-CHANNEL MOSFET WITH DIODE")
      (fields (field (name "MANUFACTURER") "INTERNATIONAL RECTIFIER") (field (name "AUTHOR") "CERN DEM JLC"))
      (libsource (lib "ICs And Semiconductors") (part "N-MOSFET-D 1G 2S 3D"))
    )
    (comp (ref "Q12")
      (value "MMBT5551")
      (footprint "SOT95P240X130-3N")
      (description "NPN Transistor")
      (fields
        (field (name "PART NUMBER") "MMBT5551L")
        (field (name "MANUFACTURER") "ON SEMICONDICTOR")
        (field (name "AUTHOR") "DEL")
      )
      (libsource (lib "ICs And Semiconductors") (part "NPN B1 E2 C3"))
    )
    (comp (ref "Q13")
      (value "CSD18531")
      (footprint "DFN-5X6-8L")
      (fields
        (field (name "PART NUMBER") "CSD18531Q5A")
        (field (name "MANUFACTURER") "TEXAS INSTRUMENTS")
        (field (name "AUTHOR") "DEL")
      )
      (libsource (lib "ICs And Semiconductors") (part "N-MOSFET-D 1-3S 4G 5-8D"))
    )
    (comp (ref "Q14")
      (value "IRFHM9331")
      (footprint "PQFN50P300X300X100_HS-9N")
      (description "P-CHANNEL MOSFET WITH DIODE")
      (fields
        (field (name "PART NUMBER") "IRFHM9331TRPbF")
        (field (name "MANUFACTURER") "INFINEON")
        (field (name "AUTHOR") "DEL")
      )
      (libsource (lib "ICs And Semiconductors") (part "P-MOSFET-D 1-3S 4G 5-8D"))
    )
    (comp (ref "R1")
      (value "2k2")
      (footprint "RESC1005X40N")
      (description "Resistor - 1%")
      (fields
        (field (name "PART NUMBER") "R0402_2K2_1%_0.0625W_100PPM")
        (field (name "POWER") "0.0625W")
        (field (name "AUTHOR") "CERN DEM JLC")
      )
      (libsource (lib "Resistors") (part "Resistor - 1%"))
    )
    (comp (ref "R2")
      (value "2k2")
      (footprint "RESC1005X40N")
      (description "Resistor - 1%")
      (fields
        (field (name "PART NUMBER") "R0402_2K2_1%_0.0625W_100PPM")
        (field (name "POWER") "0.0625W")
        (field (name "AUTHOR") "CERN DEM JLC")
      )
      (libsource (lib "Resistors") (part "Resistor - 1%"))
    )
    (comp (ref "R3")
      (value "100k")
      (footprint "RESC2012X60N")
      (description "Resistor - 1%")
      (fields
        (field (name "PART NUMBER") "R0805_100K_1%_0.125W_100PPM")
        (field (name "POWER") "0.125W")
        (field (name "AUTHOR") "CERN DEM JLC")
      )
      (libsource (lib "Resistors") (part "Resistor - 1%"))
    )
    (comp (ref "R4")
      (value "1k")
      (footprint "RESC1005X40N")
      (description "Resistor - 1%")
      (fields
        (field (name "PART NUMBER") "R0402_1K_1%_0.0625W_100PPM")
        (field (name "POWER") "0.0625W")
        (field (name "AUTHOR") "CERN DEM JLC")
      )
      (libsource (lib "Resistors") (part "Resistor - 1%"))
    )
    (comp (ref "R5")
      (value "100")
      (footprint "RESC1005X40N")
      (description "Resistor - 1%")
      (fields
        (field (name "PART NUMBER") "R0402_100R_1%_0.0625W_100PPM")
        (field (name "POWER") "0.0625W")
        (field (name "AUTHOR") "CERN DEM JLC")
      )
      (libsource (lib "Resistors") (part "Resistor - 1%"))
    )
    (comp (ref "R6")
      (value "100")
      (footprint "RESC1005X40N")
      (description "Resistor - 1%")
      (fields
        (field (name "PART NUMBER") "R0402_100R_1%_0.0625W_100PPM")
        (field (name "POWER") "0.0625W")
        (field (name "AUTHOR") "CERN DEM JLC")
      )
      (libsource (lib "Resistors") (part "Resistor - 1%"))
    )
    (comp (ref "R7")
      (value "0.1")
      (footprint "RESC1608X55N")
      (description "Resistor - 1%")
      (fields
        (field (name "PART NUMBER") "R0603_0R1_1%_0.1W_100PPM")
        (field (name "POWER") "0.1W")
        (field (name "AUTHOR") "DEL")
      )
      (libsource (lib "Resistors") (part "Resistor - 1%"))
    )
    (comp (ref "R8")
      (value "1k")
      (footprint "RESC1005X40N")
      (description "Resistor - 1%")
      (fields
        (field (name "PART NUMBER") "R0402_1K_1%_0.0625W_100PPM")
        (field (name "POWER") "0.0625W")
        (field (name "AUTHOR") "CERN DEM JLC")
      )
      (libsource (lib "Resistors") (part "Resistor - 1%"))
    )
    (comp (ref "R9")
      (value "8k2")
      (footprint "RESC1005X40N")
      (description "Resistor - 1%")
      (fields
        (field (name "PART NUMBER") "R0402_8K2_1%_0.0625W_100PPM")
        (field (name "POWER") "0.0625W")
        (field (name "AUTHOR") "CERN DEM JLC")
      )
      (libsource (lib "Resistors") (part "Resistor - 1%"))
    )
    (comp (ref "R10")
      (value "12k")
      (footprint "RESC1005X40N")
      (description "Resistor - 1%")
      (fields
        (field (name "PART NUMBER") "R0402_12K_1%_0.0625W_100PPM")
        (field (name "POWER") "0.0625W")
        (field (name "AUTHOR") "CERN DEM JLC")
      )
      (libsource (lib "Resistors") (part "Resistor - 1%"))
    )
    (comp (ref "R11")
      (value "180")
      (footprint "RESC1005X40N")
      (description "Resistor - 1%")
      (fields
        (field (name "PART NUMBER") "R0402_180R_1%_0.0625W_100PPM")
        (field (name "POWER") "0.0625W")
        (field (name "AUTHOR") "CERN DEM JLC")
      )
      (libsource (lib "Resistors") (part "Resistor - 1%"))
    )
    (comp (ref "R12")
      (value "2k2")
      (footprint "RESC1005X40N")
      (description "Resistor - 1%")
      (fields
        (field (name "PART NUMBER") "R0402_2K2_1%_0.0625W_100PPM")
        (field (name "POWER") "0.0625W")
        (field (name "AUTHOR") "CERN DEM JLC")
      )
      (libsource (lib "Resistors") (part "Resistor - 1%"))
    )
    (comp (ref "R13")
      (value "75k")
      (footprint "RESC1005X40N")
      (description "Resistor - 1%")
      (fields
        (field (name "PART NUMBER") "R0402_75K_1%_0.0625W_100PPM")
        (field (name "POWER") "0.0625W")
        (field (name "AUTHOR") "CERN DEM JLC")
      )
      (libsource (lib "Resistors") (part "Resistor - 1%"))
    )
    (comp (ref "R14")
      (value "2k2")
      (footprint "RESC2012X60N")
      (description "Resistor - 1%")
      (fields
        (field (name "PART NUMBER") "R0805_2K2_1%_0.125W_100PPM")
        (field (name "POWER") "0.125W")
        (field (name "AUTHOR") "CERN DEM JLC")
      )
      (libsource (lib "Resistors") (part "Resistor - 1%"))
    )
    (comp (ref "R15")
      (value "2k2")
      (footprint "RESC2012X60N")
      (description "Resistor - 1%")
      (fields
        (field (name "PART NUMBER") "R0805_2K2_1%_0.125W_100PPM")
        (field (name "POWER") "0.125W")
        (field (name "AUTHOR") "CERN DEM JLC")
      )
      (libsource (lib "Resistors") (part "Resistor - 1%"))
    )
    (comp (ref "R16")
      (value "2k2")
      (footprint "RESC2012X60N")
      (description "Resistor - 1%")
      (fields
        (field (name "PART NUMBER") "R0805_2K2_1%_0.125W_100PPM")
        (field (name "POWER") "0.125W")
        (field (name "AUTHOR") "CERN DEM JLC")
      )
      (libsource (lib "Resistors") (part "Resistor - 1%"))
    )
    (comp (ref "R17")
      (value "2k2")
      (footprint "RESC2012X60N")
      (description "Resistor - 1%")
      (fields
        (field (name "PART NUMBER") "R0805_2K2_1%_0.125W_100PPM")
        (field (name "POWER") "0.125W")
        (field (name "AUTHOR") "CERN DEM JLC")
      )
      (libsource (lib "Resistors") (part "Resistor - 1%"))
    )
    (comp (ref "R18")
      (value "2k")
      (footprint "RESC1005X40N")
      (description "Resistor - 1%")
      (fields
        (field (name "PART NUMBER") "R0402_2K_1%_0.0625W_100PPM")
        (field (name "POWER") "0.0625W")
        (field (name "AUTHOR") "CERN DEM JLC")
      )
      (libsource (lib "Resistors") (part "Resistor - 1%"))
    )
    (comp (ref "R19")
      (value "1k")
      (footprint "RESC1608X55N")
      (description "Resistor - 1%")
      (fields
        (field (name "PART NUMBER") "R0603_1K_1%_0.1W_100PPM")
        (field (name "POWER") "0.1W")
        (field (name "AUTHOR") "CERN DEM JLC")
      )
      (libsource (lib "Resistors") (part "Resistor - 1%"))
    )
    (comp (ref "R20")
      (value "20k")
      (footprint "RESC2012X60N")
      (description "Resistor - 1%")
      (fields
        (field (name "PART NUMBER") "R0805_20K_1%_0.125W_100PPM")
        (field (name "POWER") "0.125W")
        (field (name "AUTHOR") "CERN DEM JLC")
      )
      (libsource (lib "Resistors") (part "Resistor - 1%"))
    )
    (comp (ref "R21")
      (value "100")
      (footprint "RESC2012X60N")
      (description "Resistor - 1%")
      (fields
        (field (name "PART NUMBER") "R0805_100R_1%_0.125W_100PPM")
        (field (name "POWER") "0.125W")
        (field (name "AUTHOR") "CERN DEM JLC")
      )
      (libsource (lib "Resistors") (part "Resistor - 1%"))
    )
    (comp (ref "R22")
      (value "2k")
      (footprint "RESC1005X40N")
      (description "Resistor - 1%")
      (fields
        (field (name "PART NUMBER") "R0402_2K_1%_0.0625W_100PPM")
        (field (name "POWER") "0.0625W")
        (field (name "AUTHOR") "CERN DEM JLC")
      )
      (libsource (lib "Resistors") (part "Resistor - 1%"))
    )
    (comp (ref "R23")
      (value "2k")
      (footprint "RESC1005X40N")
      (description "Resistor - 1%")
      (fields
        (field (name "PART NUMBER") "R0402_2K_1%_0.0625W_100PPM")
        (field (name "POWER") "0.0625W")
        (field (name "AUTHOR") "CERN DEM JLC")
      )
      (libsource (lib "Resistors") (part "Resistor - 1%"))
    )
    (comp (ref "R24")
      (value "43k")
      (footprint "RESC1005X40N")
      (description "Resistor - 1%")
      (fields
        (field (name "PART NUMBER") "R0402_43K_1%_0.0625W_100PPM")
        (field (name "POWER") "0.0625W")
        (field (name "AUTHOR") "CERN DEM JLC")
      )
      (libsource (lib "Resistors") (part "Resistor - 1%"))
    )
    (comp (ref "R25")
      (value "1k")
      (footprint "RESC1005X40N")
      (description "Resistor - 1%")
      (fields
        (field (name "PART NUMBER") "R0402_1K_1%_0.0625W_100PPM")
        (field (name "POWER") "0.0625W")
        (field (name "AUTHOR") "CERN DEM JLC")
      )
      (libsource (lib "Resistors") (part "Resistor - 1%"))
    )
    (comp (ref "R26")
      (value "1")
      (footprint "RESC6331X70N")
      (description "Resistor - 1%")
      (fields
        (field (name "PART NUMBER") "R2512_1R0_1%_1W_100PPM")
        (field (name "POWER") "1W")
        (field (name "AUTHOR") "DEL")
      )
      (libsource (lib "Resistors") (part "Resistor - 1%"))
    )
    (comp (ref "R27")
      (value "120k")
      (footprint "RESC1005X40N")
      (description "Resistor - 1%")
      (fields
        (field (name "PART NUMBER") "R0402_120K_1%_0.0625W_100PPM")
        (field (name "POWER") "0.0625W")
        (field (name "AUTHOR") "CERN DEM JLC")
      )
      (libsource (lib "Resistors") (part "Resistor - 1%"))
    )
    (comp (ref "R28")
      (value "50m")
      (footprint "FC4L64_OHM")
      (description "Power and Current Sensing Resistor")
      (fields
        (field (name "PART NUMBER") "FC4L64R050FER")
        (field (name "POWER") "2W")
        (field (name "AUTHOR") "DEL")
      )
      (libsource (lib "Resistors") (part "Current Sense Resistor 2"))
    )
    (comp (ref "R29")
      (value "100")
      (footprint "RESC1005X40N")
      (description "Resistor - 1%")
      (fields
        (field (name "PART NUMBER") "R0402_100R_1%_0.0625W_100PPM")
        (field (name "POWER") "0.0625W")
        (field (name "AUTHOR") "CERN DEM JLC")
      )
      (libsource (lib "Resistors") (part "Resistor - 1%"))
    )
    (comp (ref "R30")
      (value "100")
      (footprint "RESC1005X40N")
      (description "Resistor - 1%")
      (fields
        (field (name "PART NUMBER") "R0402_100R_1%_0.0625W_100PPM")
        (field (name "POWER") "0.0625W")
        (field (name "AUTHOR") "CERN DEM JLC")
      )
      (libsource (lib "Resistors") (part "Resistor - 1%"))
    )
    (comp (ref "R31")
      (value "100")
      (footprint "RESC1005X40N")
      (description "Resistor - 1%")
      (fields
        (field (name "PART NUMBER") "R0402_100R_1%_0.0625W_100PPM")
        (field (name "POWER") "0.0625W")
        (field (name "AUTHOR") "CERN DEM JLC")
      )
      (libsource (lib "Resistors") (part "Resistor - 1%"))
    )
    (comp (ref "R32")
      (value "100")
      (footprint "RESC1005X40N")
      (description "Resistor - 1%")
      (fields
        (field (name "PART NUMBER") "R0402_100R_1%_0.0625W_100PPM")
        (field (name "POWER") "0.0625W")
        (field (name "AUTHOR") "CERN DEM JLC")
      )
      (libsource (lib "Resistors") (part "Resistor - 1%"))
    )
    (comp (ref "R33")
      (value "680")
      (footprint "RESC1005X40N")
      (description "Resistor - 0.1%")
      (fields
        (field (name "PART NUMBER") "R0402_680R_0.1%_0.063W_10PPM")
        (field (name "POWER") "0.0625W")
        (field (name "AUTHOR") "DEL")
      )
      (libsource (lib "Resistors") (part "Resistor - 0.1%"))
    )
    (comp (ref "R34")
      (value "255")
      (footprint "RESC1005X40N")
      (description "Resistor - 0.1%")
      (fields
        (field (name "PART NUMBER") "R0402_255R_0.1%_0.063W_10PPM")
        (field (name "POWER") "0.0625W")
        (field (name "AUTHOR") "DEL")
      )
      (libsource (lib "Resistors") (part "Resistor - 0.1%"))
    )
    (comp (ref "R35")
      (value "100k")
      (footprint "RESC2012X60N")
      (description "Resistor - 1%")
      (fields
        (field (name "PART NUMBER") "R0805_100K_1%_0.125W_100PPM")
        (field (name "POWER") "0.125W")
        (field (name "AUTHOR") "CERN DEM JLC")
      )
      (libsource (lib "Resistors") (part "Resistor - 1%"))
    )
    (comp (ref "R36")
      (value "4k7")
      (footprint "RESC1005X40N")
      (description "Resistor - 1%")
      (fields
        (field (name "PART NUMBER") "R0402_4K7_1%_0.0625W_100PPM")
        (field (name "POWER") "0.0625W")
        (field (name "AUTHOR") "CERN DEM JLC")
      )
      (libsource (lib "Resistors") (part "Resistor - 1%"))
    )
    (comp (ref "R37")
      (value "10k")
      (footprint "RESC1005X40N")
      (description "Resistor - 1%")
      (fields
        (field (name "PART NUMBER") "R0402_10K_1%_0.0625W_100PPM")
        (field (name "POWER") "0.0625W")
        (field (name "AUTHOR") "CERN DEM JLC")
      )
      (libsource (lib "Resistors") (part "Resistor - 1%"))
    )
    (comp (ref "R38")
      (value "100k")
      (footprint "RESC2012X60N")
      (description "Resistor - 1%")
      (fields
        (field (name "PART NUMBER") "R0805_100K_1%_0.125W_100PPM")
        (field (name "POWER") "0.125W")
        (field (name "AUTHOR") "CERN DEM JLC")
      )
      (libsource (lib "Resistors") (part "Resistor - 1%"))
    )
    (comp (ref "R39")
      (value "4k7")
      (footprint "RESC1005X40N")
      (description "Resistor - 1%")
      (fields
        (field (name "PART NUMBER") "R0402_4K7_1%_0.0625W_100PPM")
        (field (name "POWER") "0.0625W")
        (field (name "AUTHOR") "CERN DEM JLC")
      )
      (libsource (lib "Resistors") (part "Resistor - 1%"))
    )
    (comp (ref "R40")
      (value "12k")
      (footprint "RESC1005X40N")
      (description "Resistor - 0.1%")
      (fields
        (field (name "PART NUMBER") "R0402_12K_0.1%_0.063W_10PPM")
        (field (name "POWER") "0.0625W")
        (field (name "AUTHOR") "DEL")
      )
      (libsource (lib "Resistors") (part "Resistor - 0.1%"))
    )
    (comp (ref "R41")
      (value "75")
      (footprint "RESC1005X40N")
      (description "Resistor - 0.1%")
      (fields
        (field (name "PART NUMBER") "R0402_75R_0.1%_0.063W_10PPM")
        (field (name "POWER") "0.0625W")
        (field (name "AUTHOR") "DEL")
      )
      (libsource (lib "Resistors") (part "Resistor - 0.1%"))
    )
    (comp (ref "R42")
      (value "10k")
      (footprint "RESC1005X40N")
      (description "Resistor - 1%")
      (fields
        (field (name "PART NUMBER") "R0402_10K_1%_0.0625W_100PPM")
        (field (name "POWER") "0.0625W")
        (field (name "AUTHOR") "CERN DEM JLC")
      )
      (libsource (lib "Resistors") (part "Resistor - 1%"))
    )
    (comp (ref "R43")
      (value "12k")
      (footprint "RESC1005X40N")
      (description "Resistor - 1%")
      (fields
        (field (name "PART NUMBER") "R0402_12K_1%_0.0625W_100PPM")
        (field (name "POWER") "0.0625W")
        (field (name "AUTHOR") "CERN DEM JLC")
      )
      (libsource (lib "Resistors") (part "Resistor - 1%"))
    )
    (comp (ref "R44")
      (value "8k2")
      (footprint "RESC1005X40N")
      (description "Resistor - 1%")
      (fields
        (field (name "PART NUMBER") "R0402_8K2_1%_0.0625W_100PPM")
        (field (name "POWER") "0.0625W")
        (field (name "AUTHOR") "CERN DEM JLC")
      )
      (libsource (lib "Resistors") (part "Resistor - 1%"))
    )
    (comp (ref "R45")
      (value "100k")
      (footprint "RESC2012X60N")
      (description "Resistor - 1%")
      (fields
        (field (name "PART NUMBER") "R0805_100K_1%_0.125W_100PPM")
        (field (name "POWER") "0.125W")
        (field (name "AUTHOR") "CERN DEM JLC")
      )
      (libsource (lib "Resistors") (part "Resistor - 1%"))
    )
    (comp (ref "R46")
      (value "4k7")
      (footprint "RESC1005X40N")
      (description "Resistor - 1%")
      (fields
        (field (name "PART NUMBER") "R0402_4K7_1%_0.0625W_100PPM")
        (field (name "POWER") "0.0625W")
        (field (name "AUTHOR") "CERN DEM JLC")
      )
      (libsource (lib "Resistors") (part "Resistor - 1%"))
    )
    (comp (ref "R47")
      (value "100k")
      (footprint "RESC2012X60N")
      (description "Resistor - 1%")
      (fields
        (field (name "PART NUMBER") "R0805_100K_1%_0.125W_100PPM")
        (field (name "POWER") "0.125W")
        (field (name "AUTHOR") "CERN DEM JLC")
      )
      (libsource (lib "Resistors") (part "Resistor - 1%"))
    )
    (comp (ref "R48")
      (value "4k7")
      (footprint "RESC1005X40N")
      (description "Resistor - 1%")
      (fields
        (field (name "PART NUMBER") "R0402_4K7_1%_0.0625W_100PPM")
        (field (name "POWER") "0.0625W")
        (field (name "AUTHOR") "CERN DEM JLC")
      )
      (libsource (lib "Resistors") (part "Resistor - 1%"))
    )
    (comp (ref "R49")
      (value "100k")
      (footprint "RESC1005X40N")
      (description "Resistor - 0.1%")
      (fields
        (field (name "PART NUMBER") "R0402_100K_0.1%_0.063W_10PPM")
        (field (name "POWER") "0.0625W")
        (field (name "AUTHOR") "DEL")
      )
      (libsource (lib "Resistors") (part "Resistor - 0.1%"))
    )
    (comp (ref "R50")
      (value "100k")
      (footprint "RESC1005X40N")
      (description "Resistor - 0.1%")
      (fields
        (field (name "PART NUMBER") "R0402_100K_0.1%_0.063W_10PPM")
        (field (name "POWER") "0.0625W")
        (field (name "AUTHOR") "DEL")
      )
      (libsource (lib "Resistors") (part "Resistor - 0.1%"))
    )
    (comp (ref "R51")
      (value "100k")
      (footprint "RESC2012X60N")
      (description "Resistor - 1%")
      (fields
        (field (name "PART NUMBER") "R0805_100K_1%_0.125W_100PPM")
        (field (name "POWER") "0.125W")
        (field (name "AUTHOR") "CERN DEM JLC")
      )
      (libsource (lib "Resistors") (part "Resistor - 1%"))
    )
    (comp (ref "R52")
      (value "4k7")
      (footprint "RESC1005X40N")
      (description "Resistor - 1%")
      (fields
        (field (name "PART NUMBER") "R0402_4K7_1%_0.0625W_100PPM")
        (field (name "POWER") "0.0625W")
        (field (name "AUTHOR") "CERN DEM JLC")
      )
      (libsource (lib "Resistors") (part "Resistor - 1%"))
    )
    (comp (ref "R53")
      (value "1")
      (footprint "RESC2012X60N")
      (description "Resistor - 1%")
      (fields
        (field (name "PART NUMBER") "R0805_1R_1%_0.125W_200PPM")
        (field (name "POWER") "0.125W")
        (field (name "AUTHOR") "CERN DEM JLC")
      )
      (libsource (lib "Resistors") (part "Resistor - 1%"))
    )
    (comp (ref "R54")
      (value "8k45")
      (footprint "RESC1005X40N")
      (description "Resistor - 0.1%")
      (fields
        (field (name "PART NUMBER") "R0402_8K45_0.1%_0.063W_10PPM")
        (field (name "POWER") "0.0625W")
        (field (name "AUTHOR") "DEL")
      )
      (libsource (lib "Resistors") (part "Resistor - 0.1%"))
    )
    (comp (ref "R55")
      (value "8k45")
      (footprint "RESC1005X40N")
      (description "Resistor - 0.1%")
      (fields
        (field (name "PART NUMBER") "R0402_8K45_0.1%_0.063W_10PPM")
        (field (name "POWER") "0.0625W")
        (field (name "AUTHOR") "DEL")
      )
      (libsource (lib "Resistors") (part "Resistor - 0.1%"))
    )
    (comp (ref "R56")
      (value "4k7")
      (footprint "RESC1005X40N")
      (description "Resistor - 1%")
      (fields
        (field (name "PART NUMBER") "R0402_4K7_1%_0.0625W_100PPM")
        (field (name "POWER") "0.0625W")
        (field (name "AUTHOR") "CERN DEM JLC")
      )
      (libsource (lib "Resistors") (part "Resistor - 1%"))
    )
    (comp (ref "R57")
      (value "100")
      (footprint "RESC1005X40N")
      (description "Resistor - 1%")
      (fields
        (field (name "PART NUMBER") "R0402_100R_1%_0.0625W_100PPM")
        (field (name "POWER") "0.0625W")
        (field (name "AUTHOR") "CERN DEM JLC")
      )
      (libsource (lib "Resistors") (part "Resistor - 1%"))
    )
    (comp (ref "R58")
      (value "0")
      (footprint "RESC1005X40N")
      (description "Resistor - 1%")
      (fields
        (field (name "PART NUMBER") "R0402_0R_JUMPER")
        (field (name "MANUFACTURER") "GENERIC")
        (field (name "AUTHOR") "CERN DEM JLC")
      )
      (libsource (lib "Resistors") (part "Resistor - 1%"))
    )
    (comp (ref "R59")
      (value "100")
      (footprint "RESC1005X40N")
      (description "Resistor - 1%")
      (fields
        (field (name "PART NUMBER") "R0402_100R_1%_0.0625W_100PPM")
        (field (name "POWER") "0.0625W")
        (field (name "AUTHOR") "CERN DEM JLC")
      )
      (libsource (lib "Resistors") (part "Resistor - 1%"))
    )
    (comp (ref "R60")
      (value "0")
      (footprint "RESC1005X40N")
      (description "Resistor - 1%")
      (fields
        (field (name "PART NUMBER") "R0402_0R_JUMPER")
        (field (name "MANUFACTURER") "GENERIC")
        (field (name "AUTHOR") "CERN DEM JLC")
      )
      (libsource (lib "Resistors") (part "Resistor - 1%"))
    )
    (comp (ref "R61")
      (value "10k")
      (footprint "RESC1005X40N")
      (description "Resistor - 1%")
      (fields
        (field (name "PART NUMBER") "R0402_10K_1%_0.0625W_100PPM")
        (field (name "POWER") "0.0625W")
        (field (name "AUTHOR") "CERN DEM JLC")
      )
      (libsource (lib "Resistors") (part "Resistor - 1%"))
    )
    (comp (ref "R62")
      (value "10k")
      (footprint "RESC1005X40N")
      (description "Resistor - 1%")
      (fields
        (field (name "PART NUMBER") "R0402_10K_1%_0.0625W_100PPM")
        (field (name "POWER") "0.0625W")
        (field (name "AUTHOR") "CERN DEM JLC")
      )
      (libsource (lib "Resistors") (part "Resistor - 1%"))
    )
    (comp (ref "R63")
      (value "1k")
      (footprint "RESC1005X40N")
      (description "Resistor - 1%")
      (fields
        (field (name "PART NUMBER") "R0402_1K_1%_0.0625W_100PPM")
        (field (name "POWER") "0.0625W")
        (field (name "AUTHOR") "CERN DEM JLC")
      )
      (libsource (lib "Resistors") (part "Resistor - 1%"))
    )
    (comp (ref "R64")
      (value "13k")
      (footprint "RESC1005X40N")
      (description "Resistor - 1%")
      (fields
        (field (name "PART NUMBER") "R0402_13K_1%_0.0625W_100PPM")
        (field (name "POWER") "0.0625W")
        (field (name "AUTHOR") "CERN DEM JLC")
      )
      (libsource (lib "Resistors") (part "Resistor - 1%"))
    )
    (comp (ref "R65")
      (value "13k")
      (footprint "RESC1005X40N")
      (description "Resistor - 1%")
      (fields
        (field (name "PART NUMBER") "R0402_13K_1%_0.0625W_100PPM")
        (field (name "POWER") "0.0625W")
        (field (name "AUTHOR") "CERN DEM JLC")
      )
      (libsource (lib "Resistors") (part "Resistor - 1%"))
    )
    (comp (ref "TP1")
      (value "GND")
      (footprint "TP_SMD_800")
      (description "Test Point")
      (fields (field (name "PART NUMBER") "TP_SMD_0.8MM") (field (name "AUTHOR") "DEL"))
      (libsource (lib "Eletro-mechanical") (part "Test Point"))
    )
    (comp (ref "TP2")
      (value "GND")
      (footprint "TP_SMD_800")
      (description "Test Point")
      (fields (field (name "PART NUMBER") "TP_SMD_0.8MM") (field (name "AUTHOR") "DEL"))
      (libsource (lib "Eletro-mechanical") (part "Test Point"))
    )
    (comp (ref "TP3")
      (value "-4.5V")
      (footprint "TP_SMD_800")
      (description "Test Point")
      (fields (field (name "PART NUMBER") "TP_SMD_0.8MM") (field (name "AUTHOR") "DEL"))
      (libsource (lib "Eletro-mechanical") (part "Test Point"))
    )
    (comp (ref "TP4")
      (value "+REF")
      (footprint "TP_SMD_800")
      (description "Test Point")
      (fields (field (name "PART NUMBER") "TP_SMD_0.8MM") (field (name "AUTHOR") "DEL"))
      (libsource (lib "Eletro-mechanical") (part "Test Point"))
    )
    (comp (ref "TP5")
      (value "Test Point")
      (footprint "TP_SMD_800")
      (fields (field (name "PART NUMBER") "TP_SMD_0.8MM") (field (name "AUTHOR") "DEL"))
      (libsource (lib "Eletro-mechanical") (part "Test Point"))
    )
    (comp (ref "TP6")
      (value "Test Point")
      (footprint "TP_SMD_800")
      (fields (field (name "PART NUMBER") "TP_SMD_0.8MM") (field (name "AUTHOR") "DEL"))
      (libsource (lib "Eletro-mechanical") (part "Test Point"))
    )
    (comp (ref "U1")
      (value "DS18B20")
      (footprint "TO-92-H-OUTSIDE")
      (fields
        (field (name "PART NUMBER") "DS18B20_h_outside")
        (field (name "MANUFACTURER") "MAXIM")
        (field (name "AUTHOR") "DEL")
      )
      (libsource (lib "ICs And Semiconductors") (part "DS18B20"))
    )
    (comp (ref "U2")
      (value "AD8608")
      (footprint "SOP65P640X110-14N")
      (description "Quad Operational Amplifier")
      (fields
        (field (name "PART NUMBER") "AD8608ARUZ-REEL")
        (field (name "MANUFACTURER") "ANALOG DEVICES")
        (field (name "AUTHOR") "DEL")
      )
      (libsource (lib "ICs And Semiconductors") (part "Operational Amplifier x4 Type1"))
    )
    (comp (ref "U3")
      (value "NUP4202")
      (footprint "SOT65P220X110-6N")
      (description "ESD Protection Diode, Low  Clamping Voltage")
      (fields
        (field (name "PART NUMBER") "NUP4202W1")
        (field (name "MANUFACTURER") "ON SEMICONDUCTOR")
        (field (name "AUTHOR") "DEL")
      )
      (libsource (lib "ICs And Semiconductors") (part "NUP4202"))
    )
    (comp (ref "U4")
      (value "AD8605")
      (footprint "SOT95P280X145-5N")
      (description "Operational Amplifier")
      (fields
        (field (name "PART NUMBER") "AD8605ARTZ")
        (field (name "MANUFACTURER") "ANALOG DEVICES")
        (field (name "AUTHOR") "DEL")
      )
      (libsource (lib "ICs And Semiconductors") (part "Operational Amplifier Type7"))
    )
    (comp (ref "U5")
      (value "LP2985A-33DBV")
      (footprint "SOT95P280X145-5N")
      (description "150mA Low-Noise Low-Dropout Regulator Whit Shutdown")
      (fields (field (name "MANUFACTURER") "TEXAS INSTRUMENTS") (field (name "AUTHOR") "CERN DEM JLC"))
      (libsource (lib "ICs And Semiconductors") (part "LP2985"))
    )
    (comp (ref "U6")
      (value "LP2985A-50DBV")
      (footprint "SOT95P280X145-5N")
      (description "150mA Low-Noise Low-Dropout Regulator Whit Shutdown")
      (fields
        (field (name "MANUFACTURER") "TEXAS INSTRUMENTS")
        (field (name "MANUFACTURER PART NUMBER") "LP2985A-50DBVRG4")
        (field (name "AUTHOR") "DEL")
      )
      (libsource (lib "ICs And Semiconductors") (part "LP2985"))
    )
    (comp (ref "U7")
      (value "KIA7812")
      (footprint "TO-220-H-OUTSIDE")
      (description "3-Terminal Regulator 1=IN 2=GND 3=OUT")
      (fields
        (field (name "PART NUMBER") "KIA7812API_h_outside")
        (field (name "MANUFACTURER") "KEC")
        (field (name "AUTHOR") "DEL")
      )
      (libsource (lib "ICs And Semiconductors") (part "REG3 1IN-2GND-3OUT"))
    )
    (comp (ref "U8")
      (value "LM27761")
      (footprint "SON50P200X200X80-9N")
      (description "LM27761 Low-Noise, Regulated, Switched-Capacitor Voltage Inverter")
      (fields
        (field (name "MANUFACTURER") "TEXAS INSTRUMENTS")
        (field (name "MANUFACTURER PART NUMBER") "LM27761DSGR")
        (field (name "AUTHOR") "DEL")
      )
      (libsource (lib "ICs And Semiconductors") (part "LM27761"))
    )
    (comp (ref "U9")
      (value "TMP236")
      (footprint "SOT95P230X110-3N")
      (description "Low-Power, High-Accuracy Analog Output Temperature Sensors")
      (fields
        (field (name "PART NUMBER") "TMP236A2DBZR")
        (field (name "MANUFACTURER") "TEXAS INSTRUMENTS")
        (field (name "AUTHOR") "DEL")
      )
      (libsource (lib "ICs And Semiconductors") (part "TMP23x"))
    )
    (comp (ref "U10")
      (value "LTC6655BHMS8-3.3")
      (footprint "SOP65P490X110-8BN")
      (fields
        (field (name "MANUFACTURER") "LINEAR TECHNOLOGY")
        (field (name "MANUFACTURER PART NUMBER") "LTC3810EUH-5#PBF")
        (field (name "AUTHOR") "DEL")
      )
      (libsource (lib "ICs And Semiconductors") (part "LTC6655"))
    )
    (comp (ref "U11")
      (value "TMP236")
      (footprint "SOT95P230X110-3N")
      (description "Low-Power, High-Accuracy Analog Output Temperature Sensors")
      (fields
        (field (name "PART NUMBER") "TMP236A2DBZR")
        (field (name "MANUFACTURER") "TEXAS INSTRUMENTS")
        (field (name "AUTHOR") "DEL")
      )
      (libsource (lib "ICs And Semiconductors") (part "TMP23x"))
    )
    (comp (ref "U12")
      (value "AD8421")
      (footprint "SOP65P490X110-8BN")
      (description "3 nV/√Hz, Low Power Instrumentation Amplifier")
      (fields
        (field (name "PART NUMBER") "AD8421BRMZ-R")
        (field (name "MANUFACTURER") "ANALOG DEVICES")
        (field (name "AUTHOR") "DEL")
      )
      (libsource (lib "ICs And Semiconductors") (part "AD8421"))
    )
    (comp (ref "U13")
      (value "AD8421")
      (footprint "SOP65P490X110-8BN")
      (description "3 nV/√Hz, Low Power Instrumentation Amplifier")
      (fields
        (field (name "PART NUMBER") "AD8421BRMZ-R")
        (field (name "MANUFACTURER") "ANALOG DEVICES")
        (field (name "AUTHOR") "DEL")
      )
      (libsource (lib "ICs And Semiconductors") (part "AD8421"))
    )
    (comp (ref "U14")
      (value "LMC7101")
      (footprint "SOT95P280X145-5N")
      (description "Operational Amplifier")
      (fields
        (field (name "PART NUMBER") "LMC7101AIM5X/NOPB")
        (field (name "MANUFACTURER") "TEXAS INSTRUMENTS")
        (field (name "AUTHOR") "DEL")
      )
      (libsource (lib "ICs And Semiconductors") (part "Operational Amplifier Type11"))
    )
    (comp (ref "U15")
      (value "AD8605")
      (footprint "SOT95P280X145-5N")
      (description "Operational Amplifier")
      (fields
        (field (name "PART NUMBER") "AD8605ARTZ")
        (field (name "MANUFACTURER") "ANALOG DEVICES")
        (field (name "AUTHOR") "DEL")
      )
      (libsource (lib "ICs And Semiconductors") (part "Operational Amplifier Type7"))
    )
    (comp (ref "U16")
      (value "AD8605")
      (footprint "SOT95P280X145-5N")
      (description "Operational Amplifier")
      (fields
        (field (name "PART NUMBER") "AD8605ARTZ")
        (field (name "MANUFACTURER") "ANALOG DEVICES")
        (field (name "AUTHOR") "DEL")
      )
      (libsource (lib "ICs And Semiconductors") (part "Operational Amplifier Type7"))
    )
    (comp (ref "U17")
      (value "AD5060")
      (footprint "SOT65P280X145-8N")
      (fields
        (field (name "PART NUMBER") "AD5060BRJZ")
        (field (name "MANUFACTURER") "ANALOG DEVICES")
        (field (name "AUTHOR") "DEL")
      )
      (libsource (lib "ICs And Semiconductors") (part "AD5060"))
    )
    (comp (ref "U18")
      (value "TS5A3159")
      (footprint "SOT65P210X110-6N")
      (description "1-Ω SPDT Analog Switch")
      (fields
        (field (name "PART NUMBER") "TS5A3159DCKR")
        (field (name "MANUFACTURER") "TEXAS INSTRUMENTS")
        (field (name "AUTHOR") "DEL")
      )
      (libsource (lib "ICs And Semiconductors") (part "TS5A3159"))
    )
    (comp (ref "U19")
      (value "STM32F373CCT6")
      (footprint "QFP50P900X900X160-48N")
      (fields (field (name "MANUFACTURER") "ST Microelectronics") (field (name "AUTHOR") "D_EL"))
      (libsource (lib "ICs And Semiconductors") (part "STM32F373CxT"))
    )
    (comp (ref "U20")
      (value "AD4680")
      (footprint "QFN50P300X300X80-17N-D")
      (description "Differential Inputs, 1 MSPS/500 kSPS, Dual Simultaneous Sampling SAR ADCs")
      (fields
        (field (name "MANUFACTURER") "ANALOG DEVICES")
        (field (name "MANUFACTURER PART NUMBER") "AD4680BCPZ-RL7")
        (field (name "AUTHOR") "DEL")
      )
      (libsource (lib "ICs And Semiconductors") (part "AD468x"))
    )
    (comp (ref "U21")
      (value "AD5060")
      (footprint "SOT65P280X145-8N")
      (fields
        (field (name "PART NUMBER") "AD5060BRJZ")
        (field (name "MANUFACTURER") "ANALOG DEVICES")
        (field (name "AUTHOR") "DEL")
      )
      (libsource (lib "ICs And Semiconductors") (part "AD5060"))
    )
    (comp (ref "U22")
      (value "AD8606")
      (footprint "SOP65P490X110-8BN")
      (description "Dual Operational Amplifier")
      (fields
        (field (name "PART NUMBER") "AD8606ARMZ-REEL")
        (field (name "MANUFACTURER") "ANALOG DEVICES")
        (field (name "AUTHOR") "DEL")
      )
      (libsource (lib "ICs And Semiconductors") (part "Operational Amplifier x2 Type1"))
    )
    (comp (ref "X1")
      (value "24MHZ")
      (footprint "OSCCC160X200X65-4N")
      (description "Crystal 4 pins 1=XTAL 2=GND3=XTAL 4=GND")
      (fields
        (field (name "PART NUMBER") "24MHZ_XRCGB24M000F3M00R0")
        (field (name "MANUFACTURER") "MURATA")
        (field (name "AUTHOR") "D_EL")
      )
      (libsource (lib "Crystals & Oscillators") (part "Quartz Crystal 1X 2GND 3X 4GND"))
    )
  )
  (nets
    (net (code "1") (name "+5V") (class "Default")
      (node (ref "C15") (pin "2") (pinfunction "2_2") (pintype "passive"))
      (node (ref "C16") (pin "2") (pinfunction "2_2") (pintype "passive"))
      (node (ref "C22") (pin "2") (pinfunction "2_2") (pintype "passive"))
      (node (ref "C24") (pin "1") (pinfunction "1_1") (pintype "passive"))
      (node (ref "C25") (pin "1") (pinfunction "1_1") (pintype "passive"))
      (node (ref "C26") (pin "2") (pinfunction "2_2") (pintype "passive"))
      (node (ref "C27") (pin "2") (pinfunction "2_2") (pintype "passive"))
      (node (ref "C38") (pin "2") (pinfunction "2_2") (pintype "passive"))
      (node (ref "C40") (pin "1") (pinfunction "1_1") (pintype "passive"))
      (node (ref "C41") (pin "1") (pinfunction "1_1") (pintype "passive"))
      (node (ref "C43") (pin "2") (pinfunction "2_2") (pintype "passive"))
      (node (ref "C48") (pin "2") (pinfunction "2_2") (pintype "passive"))
      (node (ref "C49") (pin "1") (pinfunction "1_1") (pintype "passive"))
      (node (ref "C54") (pin "2") (pinfunction "2_2") (pintype "passive"))
      (node (ref "C55") (pin "2") (pinfunction "2_2") (pintype "passive"))
      (node (ref "C56") (pin "2") (pinfunction "2_2") (pintype "passive"))
      (node (ref "C57") (pin "2") (pinfunction "2_2") (pintype "passive"))
      (node (ref "C58") (pin "1") (pinfunction "1_1") (pintype "passive"))
      (node (ref "C7") (pin "1") (pinfunction "1_1") (pintype "passive"))
      (node (ref "C74") (pin "2") (pinfunction "2_2") (pintype "passive"))
      (node (ref "C76") (pin "2") (pinfunction "2_2") (pintype "passive"))
      (node (ref "L1") (pin "1") (pinfunction "1_1") (pintype "passive"))
      (node (ref "R10") (pin "2") (pinfunction "2_2") (pintype "passive"))
      (node (ref "R12") (pin "2") (pinfunction "2_2") (pintype "passive"))
      (node (ref "U11") (pin "1") (pinfunction "VDD_1") (pintype "power_in"))
      (node (ref "U12") (pin "8") (pinfunction "+Vs_8") (pintype "power_in"))
      (node (ref "U13") (pin "8") (pinfunction "+Vs_8") (pintype "power_in"))
      (node (ref "U15") (pin "5") (pinfunction "V+_5") (pintype "power_in"))
      (node (ref "U16") (pin "5") (pinfunction "V+_5") (pintype "power_in"))
      (node (ref "U17") (pin "2") (pinfunction "VDD_2") (pintype "power_in"))
      (node (ref "U18") (pin "5") (pinfunction "V+_5") (pintype "power_in"))
      (node (ref "U2") (pin "4") (pinfunction "V+_4") (pintype "power_in"))
      (node (ref "U21") (pin "2") (pinfunction "VDD_2") (pintype "power_in"))
      (node (ref "U22") (pin "8") (pinfunction "V+_8") (pintype "power_in"))
      (node (ref "U4") (pin "5") (pinfunction "V+_5") (pintype "power_in"))
      (node (ref "U6") (pin "5") (pinfunction "VOUT_5") (pintype "power_in"))
      (node (ref "U9") (pin "1") (pinfunction "VDD_1") (pintype "power_in"))
    )
    (net (code "2") (name "/+3.3V") (class "Default")
      (node (ref "C17") (pin "2") (pinfunction "2_2") (pintype "passive"))
      (node (ref "C3") (pin "2") (pinfunction "2_2") (pintype "passive"))
      (node (ref "C63") (pin "2") (pinfunction "2_2") (pintype "passive"))
      (node (ref "C64") (pin "2") (pinfunction "2_2") (pintype "passive"))
      (node (ref "C65") (pin "2") (pinfunction "2_2") (pintype "passive"))
      (node (ref "C66") (pin "1") (pinfunction "1_1") (pintype "passive"))
      (node (ref "C67") (pin "1") (pinfunction "1_1") (pintype "passive"))
      (node (ref "C68") (pin "2") (pinfunction "2_2") (pintype "passive"))
      (node (ref "C71") (pin "2") (pinfunction "2_2") (pintype "passive"))
      (node (ref "J1") (pin "1") (pinfunction "1_1") (pintype "bidirectional"))
      (node (ref "R4") (pin "2") (pinfunction "2_2") (pintype "passive"))
      (node (ref "U1") (pin "3") (pinfunction "VDD_3") (pintype "power_in"))
      (node (ref "U19") (pin "1") (pinfunction "VBAT_1") (pintype "power_in"))
      (node (ref "U19") (pin "17") (pinfunction "VDD_2_17") (pintype "bidirectional"))
      (node (ref "U19") (pin "24") (pinfunction "VDDSD_24") (pintype "power_in"))
      (node (ref "U19") (pin "48") (pinfunction "VDD_1_48") (pintype "power_in"))
      (node (ref "U19") (pin "9") (pinfunction "VDDA/VREF+_9") (pintype "power_in"))
      (node (ref "U20") (pin "2") (pinfunction "VLOGIC_2") (pintype "power_in"))
      (node (ref "U20") (pin "4") (pinfunction "VCC_4") (pintype "power_in"))
      (node (ref "U5") (pin "5") (pinfunction "VOUT_5") (pintype "power_in"))
    )
    (net (code "3") (name "/+REF") (class "Default")
      (node (ref "C28") (pin "2") (pinfunction "2_2") (pintype "passive"))
      (node (ref "C59") (pin "2") (pinfunction "2_2") (pintype "passive"))
      (node (ref "C62") (pin "2") (pinfunction "2_2") (pintype "passive"))
      (node (ref "C77") (pin "2") (pinfunction "2_2") (pintype "passive"))
      (node (ref "C80") (pin "2") (pinfunction "2_2") (pintype "passive"))
      (node (ref "R40") (pin "2") (pinfunction "2_2") (pintype "passive"))
      (node (ref "TP4") (pin "1") (pinfunction "1_1") (pintype "passive"))
      (node (ref "U10") (pin "6") (pinfunction "VOUT_S_6") (pintype "input"))
      (node (ref "U10") (pin "7") (pinfunction "VOUT_F_7") (pintype "output"))
      (node (ref "U17") (pin "3") (pinfunction "VREF_3") (pintype "input"))
      (node (ref "U19") (pin "25") (pinfunction "VREFSD+_25") (pintype "bidirectional"))
      (node (ref "U20") (pin "11") (pinfunction "REFIO_11") (pintype "bidirectional"))
      (node (ref "U21") (pin "3") (pinfunction "VREF_3") (pintype "input"))
    )
    (net (code "4") (name "/-4.5V") (class "Default")
      (node (ref "C29") (pin "2") (pinfunction "2_2") (pintype "passive"))
      (node (ref "C30") (pin "2") (pinfunction "2_2") (pintype "passive"))
      (node (ref "C31") (pin "1") (pinfunction "1_1") (pintype "passive"))
      (node (ref "C32") (pin "1") (pinfunction "1_1") (pintype "passive"))
      (node (ref "L2") (pin "2") (pinfunction "2_2") (pintype "passive"))
      (node (ref "Q10") (pin "1") (pinfunction "G_1") (pintype "passive"))
      (node (ref "R19") (pin "1") (pinfunction "1_1") (pintype "passive"))
      (node (ref "TP3") (pin "1") (pinfunction "1_1") (pintype "passive"))
      (node (ref "U12") (pin "5") (pinfunction "-Vs_5") (pintype "power_in"))
      (node (ref "U13") (pin "5") (pinfunction "-Vs_5") (pintype "power_in"))
    )
    (net (code "5") (name "/0.0725V") (class "Default")
      (node (ref "R10") (pin "1") (pinfunction "1_1") (pintype "passive"))
      (node (ref "R11") (pin "2") (pinfunction "2_2") (pintype "passive"))
      (node (ref "R13") (pin "1") (pinfunction "1_1") (pintype "passive"))
      (node (ref "U4") (pin "3") (pinfunction "IN+_3") (pintype "input"))
    )
    (net (code "6") (name "/0V") (class "Default")
      (node (ref "B11") (pin "1") (pinfunction "1_1") (pintype "bidirectional"))
      (node (ref "B6") (pin "1") (pinfunction "1_1") (pintype "bidirectional"))
      (node (ref "C11") (pin "1") (pinfunction "1_1") (pintype "passive"))
      (node (ref "C13") (pin "1") (pinfunction "1_1") (pintype "passive"))
      (node (ref "C14") (pin "1") (pinfunction "1_1") (pintype "passive"))
      (node (ref "C15") (pin "1") (pinfunction "1_1") (pintype "passive"))
      (node (ref "C16") (pin "1") (pinfunction "1_1") (pintype "passive"))
      (node (ref "C17") (pin "1") (pinfunction "1_1") (pintype "passive"))
      (node (ref "C18") (pin "1") (pinfunction "1_1") (pintype "passive"))
      (node (ref "C19") (pin "1") (pinfunction "1_1") (pintype "passive"))
      (node (ref "C20") (pin "1") (pinfunction "1_1") (pintype "passive"))
      (node (ref "C22") (pin "1") (pinfunction "1_1") (pintype "passive"))
      (node (ref "C24") (pin "2") (pinfunction "2_2") (pintype "passive"))
      (node (ref "C25") (pin "2") (pinfunction "2_2") (pintype "passive"))
      (node (ref "C26") (pin "1") (pinfunction "1_1") (pintype "passive"))
      (node (ref "C27") (pin "1") (pinfunction "1_1") (pintype "passive"))
      (node (ref "C28") (pin "1") (pinfunction "1_1") (pintype "passive"))
      (node (ref "C29") (pin "1") (pinfunction "1_1") (pintype "passive"))
      (node (ref "C3") (pin "1") (pinfunction "1_1") (pintype "passive"))
      (node (ref "C30") (pin "1") (pinfunction "1_1") (pintype "passive"))
      (node (ref "C31") (pin "2") (pinfunction "2_2") (pintype "passive"))
      (node (ref "C32") (pin "2") (pinfunction "2_2") (pintype "passive"))
      (node (ref "C33") (pin "1") (pinfunction "1_1") (pintype "passive"))
      (node (ref "C34") (pin "1") (pinfunction "1_1") (pintype "passive"))
      (node (ref "C35") (pin "1") (pinfunction "1_1") (pintype "passive"))
      (node (ref "C36") (pin "1") (pinfunction "1_1") (pintype "passive"))
      (node (ref "C37") (pin "1") (pinfunction "1_1") (pintype "passive"))
      (node (ref "C38") (pin "1") (pinfunction "1_1") (pintype "passive"))
      (node (ref "C40") (pin "2") (pinfunction "2_2") (pintype "passive"))
      (node (ref "C41") (pin "2") (pinfunction "2_2") (pintype "passive"))
      (node (ref "C42") (pin "1") (pinfunction "1_1") (pintype "passive"))
      (node (ref "C43") (pin "1") (pinfunction "1_1") (pintype "passive"))
      (node (ref "C44") (pin "1") (pinfunction "1_1") (pintype "passive"))
      (node (ref "C45") (pin "1") (pinfunction "1_1") (pintype "passive"))
      (node (ref "C46") (pin "1") (pinfunction "1_1") (pintype "passive"))
      (node (ref "C48") (pin "1") (pinfunction "1_1") (pintype "passive"))
      (node (ref "C49") (pin "2") (pinfunction "2_2") (pintype "passive"))
      (node (ref "C5") (pin "1") (pinfunction "1_1") (pintype "passive"))
      (node (ref "C50") (pin "1") (pinfunction "1_1") (pintype "passive"))
      (node (ref "C51") (pin "1") (pinfunction "1_1") (pintype "passive"))
      (node (ref "C52") (pin "1") (pinfunction "1_1") (pintype "passive"))
      (node (ref "C53") (pin "1") (pinfunction "1_1") (pintype "passive"))
      (node (ref "C54") (pin "1") (pinfunction "1_1") (pintype "passive"))
      (node (ref "C55") (pin "1") (pinfunction "1_1") (pintype "passive"))
      (node (ref "C56") (pin "1") (pinfunction "1_1") (pintype "passive"))
      (node (ref "C57") (pin "1") (pinfunction "1_1") (pintype "passive"))
      (node (ref "C58") (pin "2") (pinfunction "2_2") (pintype "passive"))
      (node (ref "C59") (pin "1") (pinfunction "1_1") (pintype "passive"))
      (node (ref "C6") (pin "1") (pinfunction "1_1") (pintype "passive"))
      (node (ref "C62") (pin "1") (pinfunction "1_1") (pintype "passive"))
      (node (ref "C63") (pin "1") (pinfunction "1_1") (pintype "passive"))
      (node (ref "C64") (pin "1") (pinfunction "1_1") (pintype "passive"))
      (node (ref "C65") (pin "1") (pinfunction "1_1") (pintype "passive"))
      (node (ref "C66") (pin "2") (pinfunction "2_2") (pintype "passive"))
      (node (ref "C67") (pin "2") (pinfunction "2_2") (pintype "passive"))
      (node (ref "C68") (pin "1") (pinfunction "1_1") (pintype "passive"))
      (node (ref "C69") (pin "1") (pinfunction "1_1") (pintype "passive"))
      (node (ref "C7") (pin "2") (pinfunction "2_2") (pintype "passive"))
      (node (ref "C70") (pin "1") (pinfunction "1_1") (pintype "passive"))
      (node (ref "C71") (pin "1") (pinfunction "1_1") (pintype "passive"))
      (node (ref "C74") (pin "1") (pinfunction "1_1") (pintype "passive"))
      (node (ref "C75") (pin "1") (pinfunction "1_1") (pintype "passive"))
      (node (ref "C76") (pin "1") (pinfunction "1_1") (pintype "passive"))
      (node (ref "C77") (pin "1") (pinfunction "1_1") (pintype "passive"))
      (node (ref "C78") (pin "1") (pinfunction "1_1") (pintype "passive"))
      (node (ref "C79") (pin "1") (pinfunction "1_1") (pintype "passive"))
      (node (ref "C8") (pin "1") (pinfunction "1_1") (pintype "passive"))
      (node (ref "C80") (pin "1") (pinfunction "1_1") (pintype "passive"))
      (node (ref "C9") (pin "1") (pinfunction "1_1") (pintype "passive"))
      (node (ref "J1") (pin "3") (pinfunction "3_3") (pintype "bidirectional"))
      (node (ref "J2") (pin "1") (pinfunction "1_1") (pintype "bidirectional"))
      (node (ref "Q1") (pin "2") (pinfunction "E_2") (pintype "passive"))
      (node (ref "Q11") (pin "2") (pinfunction "S_2") (pintype "passive"))
      (node (ref "Q12") (pin "2") (pinfunction "E_2") (pintype "passive"))
      (node (ref "Q13") (pin "1") (pinfunction "S_1") (pintype "passive"))
      (node (ref "Q13") (pin "2") (pinfunction "S_2") (pintype "passive"))
      (node (ref "Q13") (pin "3") (pinfunction "S_3") (pintype "passive"))
      (node (ref "R11") (pin "1") (pinfunction "1_1") (pintype "passive"))
      (node (ref "R20") (pin "1") (pinfunction "1_1") (pintype "passive"))
      (node (ref "R25") (pin "1") (pinfunction "1_1") (pintype "passive"))
      (node (ref "R26") (pin "1") (pinfunction "1_1") (pintype "passive"))
      (node (ref "R36") (pin "1") (pinfunction "1_1") (pintype "passive"))
      (node (ref "R39") (pin "1") (pinfunction "1_1") (pintype "passive"))
      (node (ref "R41") (pin "1") (pinfunction "1_1") (pintype "passive"))
      (node (ref "R42") (pin "1") (pinfunction "1_1") (pintype "passive"))
      (node (ref "R46") (pin "1") (pinfunction "1_1") (pintype "passive"))
      (node (ref "R48") (pin "1") (pinfunction "1_1") (pintype "passive"))
      (node (ref "R52") (pin "1") (pinfunction "1_1") (pintype "passive"))
      (node (ref "R53") (pin "1") (pinfunction "1_1") (pintype "passive"))
      (node (ref "R58") (pin "1") (pinfunction "1_1") (pintype "passive"))
      (node (ref "R60") (pin "1") (pinfunction "1_1") (pintype "passive"))
      (node (ref "R63") (pin "2") (pinfunction "2_2") (pintype "passive"))
      (node (ref "TP1") (pin "1") (pinfunction "1_1") (pintype "passive"))
      (node (ref "TP2") (pin "1") (pinfunction "1_1") (pintype "passive"))
      (node (ref "U1") (pin "1") (pinfunction "GND_1") (pintype "power_in"))
      (node (ref "U10") (pin "3") (pinfunction "GND_3") (pintype "power_in"))
      (node (ref "U10") (pin "4") (pinfunction "GND_4") (pintype "power_in"))
      (node (ref "U10") (pin "5") (pinfunction "GND_5") (pintype "power_in"))
      (node (ref "U10") (pin "8") (pinfunction "GND_8") (pintype "power_in"))
      (node (ref "U11") (pin "3") (pinfunction "GND_3") (pintype "power_in"))
      (node (ref "U14") (pin "5") (pinfunction "V-_5") (pintype "power_in"))
      (node (ref "U15") (pin "2") (pinfunction "V-_2") (pintype "power_in"))
      (node (ref "U16") (pin "2") (pinfunction "V-_2") (pintype "power_in"))
      (node (ref "U17") (pin "5") (pinfunction "AGND_5") (pintype "power_in"))
      (node (ref "U17") (pin "6") (pinfunction "DACGND_6") (pintype "power_in"))
      (node (ref "U18") (pin "2") (pinfunction "GND_2") (pintype "power_in"))
      (node (ref "U19") (pin "23") (pinfunction "VSSSD/VREFSD-_23") (pintype "power_in"))
      (node (ref "U19") (pin "44") (pinfunction "BOOT0_44") (pintype "input"))
      (node (ref "U19") (pin "47") (pinfunction "VSS_1_47") (pintype "power_in"))
      (node (ref "U19") (pin "8") (pinfunction "VSSA/VREF-_8") (pintype "power_in"))
      (node (ref "U2") (pin "11") (pinfunction "V-_11") (pintype "power_in"))
      (node (ref "U20") (pin "1") (pinfunction "GND_1") (pintype "power_in"))
      (node (ref "U20") (pin "10") (pinfunction "GND_10") (pintype "power_in"))
      (node (ref "U20") (pin "17") (pinfunction "EP_17") (pintype "power_in"))
      (node (ref "U21") (pin "5") (pinfunction "AGND_5") (pintype "power_in"))
      (node (ref "U21") (pin "6") (pinfunction "DACGND_6") (pintype "power_in"))
      (node (ref "U22") (pin "4") (pinfunction "V-_4") (pintype "power_in"))
      (node (ref "U3") (pin "2") (pinfunction "VN_2") (pintype "power_in"))
      (node (ref "U4") (pin "2") (pinfunction "V-_2") (pintype "power_in"))
      (node (ref "U5") (pin "2") (pinfunction "GND_2") (pintype "power_in"))
      (node (ref "U6") (pin "2") (pinfunction "GND_2") (pintype "power_in"))
      (node (ref "U7") (pin "2") (pinfunction "GND_2") (pintype "power_in"))
      (node (ref "U9") (pin "3") (pinfunction "GND_3") (pintype "power_in"))
      (node (ref "X1") (pin "2") (pinfunction "GND_2") (pintype "power_in"))
      (node (ref "X1") (pin "4") (pinfunction "GND_4") (pintype "power_in"))
      (node (ref "n1") (pin "1") (pinfunction "1_1") (pintype "passive"))
      (node (ref "n3") (pin "1") (pinfunction "1_1") (pintype "passive"))
    )
    (net (code "7") (name "/ADC_NSS") (class "Default")
      (node (ref "U19") (pin "38") (pinfunction "PA15_38") (pintype "bidirectional"))
      (node (ref "U20") (pin "12") (pinfunction "~{CS}_12") (pintype "input"))
    )
    (net (code "8") (name "/CC_CV") (class "Default")
      (node (ref "U19") (pin "10") (pinfunction "PA0_10") (pintype "bidirectional"))
      (node (ref "U2") (pin "8") (pinfunction "OUT_8") (pintype "output"))
    )
    (net (code "9") (name "/CON_RX") (class "Default")
      (node (ref "J2") (pin "2") (pinfunction "2_2") (pintype "bidirectional"))
      (node (ref "R5") (pin "1") (pinfunction "1_1") (pintype "passive"))
    )
    (net (code "10") (name "/CON_TX") (class "Default")
      (node (ref "J2") (pin "3") (pinfunction "3_3") (pintype "bidirectional"))
      (node (ref "R6") (pin "1") (pinfunction "1_1") (pintype "passive"))
    )
    (net (code "11") (name "/CON_VP") (class "Default")
      (node (ref "J2") (pin "4") (pinfunction "4_4") (pintype "bidirectional"))
      (node (ref "R7") (pin "1") (pinfunction "1_1") (pintype "passive"))
    )
    (net (code "12") (name "/DAC1_OUT1") (class "Default")
      (node (ref "R37") (pin "1") (pinfunction "1_1") (pintype "passive"))
      (node (ref "U19") (pin "14") (pinfunction "PA4_14") (pintype "bidirectional"))
    )
    (net (code "13") (name "/G1") (class "Default")
      (node (ref "D5") (pin "1") (pinfunction "C_1") (pintype "passive"))
      (node (ref "Q9") (pin "1") (pinfunction "G_1") (pintype "passive"))
      (node (ref "R17") (pin "1") (pinfunction "1_1") (pintype "passive"))
    )
    (net (code "14") (name "/G2") (class "Default")
      (node (ref "D4") (pin "1") (pinfunction "C_1") (pintype "passive"))
      (node (ref "Q8") (pin "1") (pinfunction "G_1") (pintype "passive"))
      (node (ref "R16") (pin "1") (pinfunction "1_1") (pintype "passive"))
    )
    (net (code "15") (name "/G3") (class "Default")
      (node (ref "D3") (pin "1") (pinfunction "C_1") (pintype "passive"))
      (node (ref "Q7") (pin "1") (pinfunction "G_1") (pintype "passive"))
      (node (ref "R15") (pin "1") (pinfunction "1_1") (pintype "passive"))
    )
    (net (code "16") (name "/G4") (class "Default")
      (node (ref "D2") (pin "1") (pinfunction "C_1") (pintype "passive"))
      (node (ref "Q6") (pin "1") (pinfunction "G_1") (pintype "passive"))
      (node (ref "R14") (pin "1") (pinfunction "1_1") (pintype "passive"))
    )
    (net (code "17") (name "/IFAN_ADC") (class "Default")
      (node (ref "C51") (pin "2") (pinfunction "2_2") (pintype "passive"))
      (node (ref "R56") (pin "2") (pinfunction "2_2") (pintype "passive"))
      (node (ref "U19") (pin "18") (pinfunction "PB0_18") (pintype "bidirectional"))
    )
    (net (code "18") (name "/IVGND") (class "Default")
      (node (ref "C10") (pin "2") (pinfunction "2_2") (pintype "passive"))
      (node (ref "C21") (pin "2") (pinfunction "2_2") (pintype "passive"))
      (node (ref "C23") (pin "2") (pinfunction "2_2") (pintype "passive"))
      (node (ref "R24") (pin "1") (pinfunction "1_1") (pintype "passive"))
      (node (ref "U8") (pin "2") (pinfunction "GND_2") (pintype "power_in"))
      (node (ref "U8") (pin "9") (pinfunction "E_9") (pintype "power_in"))
      (node (ref "n1") (pin "2") (pinfunction "2_2") (pintype "passive"))
    )
    (net (code "19") (name "/I_ADC") (class "Default")
      (node (ref "C72") (pin "2") (pinfunction "2_2") (pintype "passive"))
      (node (ref "R59") (pin "1") (pinfunction "1_1") (pintype "passive"))
      (node (ref "U22") (pin "1") (pinfunction "OUT_1") (pintype "output"))
      (node (ref "U22") (pin "2") (pinfunction "IN-_2") (pintype "input"))
    )
    (net (code "20") (name "/I_MEAS") (class "Default")
      (node (ref "R2") (pin "1") (pinfunction "1_1") (pintype "passive"))
      (node (ref "U13") (pin "7") (pinfunction "Vout_7") (pintype "output"))
      (node (ref "U18") (pin "1") (pinfunction "NO_1") (pintype "bidirectional"))
      (node (ref "U4") (pin "4") (pinfunction "IN-_4") (pintype "input"))
    )
    (net (code "21") (name "/I_MEAS_L") (class "Default")
      (node (ref "U12") (pin "7") (pinfunction "Vout_7") (pintype "output"))
      (node (ref "U18") (pin "3") (pinfunction "NC_3") (pintype "bidirectional"))
    )
    (net (code "22") (name "/I_SET") (class "Default")
      (node (ref "U17") (pin "4") (pinfunction "VOUT_4") (pintype "output"))
      (node (ref "U2") (pin "5") (pinfunction "IN+_5") (pintype "input"))
    )
    (net (code "23") (name "/LED1") (class "Default")
      (node (ref "LD2") (pin "2") (pinfunction "A_2") (pintype "passive"))
      (node (ref "U19") (pin "35") (pinfunction "PF6_35") (pintype "bidirectional"))
    )
    (net (code "24") (name "/NEG") (class "Default")
      (node (ref "B8") (pin "1") (pinfunction "1_1") (pintype "bidirectional"))
      (node (ref "R28") (pin "I1") (pinfunction "I1_I1") (pintype "passive"))
    )
    (net (code "25") (name "/NRST") (class "Default")
      (node (ref "C75") (pin "2") (pinfunction "2_2") (pintype "passive"))
      (node (ref "U19") (pin "7") (pinfunction "NRST_7") (pintype "input"))
    )
    (net (code "26") (name "/ON_OFF") (class "Default")
      (node (ref "Q1") (pin "1") (pinfunction "B_1") (pintype "passive"))
      (node (ref "R3") (pin "1") (pinfunction "1_1") (pintype "passive"))
      (node (ref "U19") (pin "43") (pinfunction "PB7_43") (pintype "bidirectional"))
    )
    (net (code "27") (name "/POS") (class "Default")
      (node (ref "B7") (pin "1") (pinfunction "1_1") (pintype "bidirectional"))
      (node (ref "Q10") (pin "3") (pinfunction "D_3") (pintype "passive"))
      (node (ref "Q9") (pin "3") (pinfunction "S_3") (pintype "passive"))
      (node (ref "R17") (pin "2") (pinfunction "2_2") (pintype "passive"))
      (node (ref "R20") (pin "2") (pinfunction "2_2") (pintype "passive"))
    )
    (net (code "28") (name "/RCC_OSC_IN") (class "Default")
      (node (ref "C52") (pin "2") (pinfunction "2_2") (pintype "passive"))
      (node (ref "U19") (pin "5") (pinfunction "PF0_5") (pintype "bidirectional"))
      (node (ref "X1") (pin "3") (pinfunction "X_3") (pintype "passive"))
    )
    (net (code "29") (name "/RCC_OSC_OUT") (class "Default")
      (node (ref "C53") (pin "2") (pinfunction "2_2") (pintype "passive"))
      (node (ref "U19") (pin "6") (pinfunction "PF1_6") (pintype "bidirectional"))
      (node (ref "X1") (pin "1") (pinfunction "X_1") (pintype "passive"))
    )
    (net (code "30") (name "/RNG") (class "Default")
      (node (ref "U18") (pin "6") (pinfunction "IN_6") (pintype "input"))
      (node (ref "U19") (pin "11") (pinfunction "PA1_11") (pintype "bidirectional"))
    )
    (net (code "31") (name "/RNG_OVF") (class "Default")
      (node (ref "R13") (pin "2") (pinfunction "2_2") (pintype "passive"))
      (node (ref "R18") (pin "1") (pinfunction "1_1") (pintype "passive"))
      (node (ref "U19") (pin "42") (pinfunction "PB6_42") (pintype "bidirectional"))
      (node (ref "U4") (pin "1") (pinfunction "OUT_1") (pintype "output"))
    )
    (net (code "32") (name "/S+") (class "Default")
      (node (ref "B9") (pin "1") (pinfunction "1_1") (pintype "bidirectional"))
      (node (ref "R49") (pin "1") (pinfunction "1_1") (pintype "passive"))
    )
    (net (code "33") (name "/S-") (class "Default")
      (node (ref "B10") (pin "1") (pinfunction "1_1") (pintype "bidirectional"))
      (node (ref "R43") (pin "1") (pinfunction "1_1") (pintype "passive"))
    )
    (net (code "34") (name "/SPI3_CLK") (class "Default")
      (node (ref "U17") (pin "8") (pinfunction "SCLK_8") (pintype "input"))
      (node (ref "U19") (pin "39") (pinfunction "PB3_39") (pintype "bidirectional"))
      (node (ref "U20") (pin "16") (pinfunction "SCLK_16") (pintype "input"))
      (node (ref "U21") (pin "8") (pinfunction "SCLK_8") (pintype "input"))
    )
    (net (code "35") (name "/SPI3_MISO") (class "Default")
      (node (ref "U19") (pin "40") (pinfunction "PB4_40") (pintype "bidirectional"))
      (node (ref "U20") (pin "13") (pinfunction "SDOA_13") (pintype "output"))
    )
    (net (code "36") (name "/SPI3_MOSI") (class "Default")
      (node (ref "U17") (pin "1") (pinfunction "DIN_1") (pintype "input"))
      (node (ref "U19") (pin "41") (pinfunction "PB5_41") (pintype "bidirectional"))
      (node (ref "U20") (pin "15") (pinfunction "SDI_15") (pintype "input"))
      (node (ref "U21") (pin "1") (pinfunction "DIN_1") (pintype "input"))
    )
    (net (code "37") (name "/SPI3_NSS2") (class "Default")
      (node (ref "U19") (pin "36") (pinfunction "PF7_36") (pintype "bidirectional"))
      (node (ref "U21") (pin "7") (pinfunction "~{SYNC}_7") (pintype "input"))
    )
    (net (code "38") (name "/SPI3_NSS3") (class "Default")
      (node (ref "U17") (pin "7") (pinfunction "~{SYNC}_7") (pintype "input"))
      (node (ref "U19") (pin "33") (pinfunction "PA12_33") (pintype "bidirectional"))
    )
    (net (code "39") (name "/SWCLK") (class "Default")
      (node (ref "J1") (pin "2") (pinfunction "2_2") (pintype "bidirectional"))
      (node (ref "U19") (pin "37") (pinfunction "PA14_37") (pintype "bidirectional"))
    )
    (net (code "40") (name "/SWDIO") (class "Default")
      (node (ref "J1") (pin "4") (pinfunction "4_4") (pintype "bidirectional"))
      (node (ref "U19") (pin "34") (pinfunction "PA13_34") (pintype "bidirectional"))
    )
    (net (code "41") (name "/TSH1") (class "Default")
      (node (ref "U19") (pin "19") (pinfunction "PB1_19") (pintype "bidirectional"))
      (node (ref "U9") (pin "2") (pinfunction "VOUT_2") (pintype "output"))
    )
    (net (code "42") (name "/TSH2") (class "Default")
      (node (ref "U11") (pin "2") (pinfunction "VOUT_2") (pintype "output"))
      (node (ref "U19") (pin "20") (pinfunction "PB2_20") (pintype "bidirectional"))
    )
    (net (code "43") (name "/UART1_RX") (class "Default")
      (node (ref "R5") (pin "2") (pinfunction "2_2") (pintype "passive"))
      (node (ref "U19") (pin "31") (pinfunction "PA10_31") (pintype "bidirectional"))
      (node (ref "U3") (pin "4") (pinfunction "I/O3_4") (pintype "bidirectional"))
    )
    (net (code "44") (name "/UART1_TX") (class "Default")
      (node (ref "R6") (pin "2") (pinfunction "2_2") (pintype "passive"))
      (node (ref "U19") (pin "30") (pinfunction "PA9_30") (pintype "bidirectional"))
      (node (ref "U3") (pin "6") (pinfunction "I/O4_6") (pintype "bidirectional"))
    )
    (net (code "45") (name "/UART2_TX") (class "Default")
      (node (ref "R4") (pin "1") (pinfunction "1_1") (pintype "passive"))
      (node (ref "U1") (pin "2") (pinfunction "DQ_2") (pintype "bidirectional"))
      (node (ref "U19") (pin "12") (pinfunction "PA2_12") (pintype "bidirectional"))
    )
    (net (code "46") (name "/UART3_RX") (class "Default")
      (node (ref "TP5") (pin "1") (pinfunction "1_1") (pintype "passive"))
      (node (ref "U19") (pin "46") (pinfunction "PB9_46") (pintype "bidirectional"))
    )
    (net (code "47") (name "/UART3_TX") (class "Default")
      (node (ref "TP6") (pin "1") (pinfunction "1_1") (pintype "passive"))
      (node (ref "U19") (pin "45") (pinfunction "PB8_45") (pintype "bidirectional"))
    )
    (net (code "48") (name "/V1") (class "Default")
      (node (ref "B5") (pin "1") (pinfunction "1_1") (pintype "bidirectional"))
      (node (ref "D1") (pin "2") (pinfunction "A_2") (pintype "passive"))
      (node (ref "D8") (pin "1") (pinfunction "A_1") (pintype "passive"))
      (node (ref "D8") (pin "3") (pinfunction "A_3") (pintype "passive"))
      (node (ref "R35") (pin "2") (pinfunction "2_2") (pintype "passive"))
    )
    (net (code "49") (name "/V1_ADC") (class "Default")
      (node (ref "C33") (pin "2") (pinfunction "2_2") (pintype "passive"))
      (node (ref "R35") (pin "1") (pinfunction "1_1") (pintype "passive"))
      (node (ref "R36") (pin "2") (pinfunction "2_2") (pintype "passive"))
      (node (ref "U19") (pin "21") (pinfunction "PE8_21") (pintype "bidirectional"))
    )
    (net (code "50") (name "/V2") (class "Default")
      (node (ref "B4") (pin "1") (pinfunction "1_1") (pintype "bidirectional"))
      (node (ref "D7") (pin "1") (pinfunction "A_1") (pintype "passive"))
      (node (ref "D7") (pin "3") (pinfunction "A_3") (pintype "passive"))
      (node (ref "R38") (pin "2") (pinfunction "2_2") (pintype "passive"))
    )
    (net (code "51") (name "/V2_ADC") (class "Default")
      (node (ref "C36") (pin "2") (pinfunction "2_2") (pintype "passive"))
      (node (ref "R38") (pin "1") (pinfunction "1_1") (pintype "passive"))
      (node (ref "R39") (pin "2") (pinfunction "2_2") (pintype "passive"))
      (node (ref "U19") (pin "22") (pinfunction "PE9_22") (pintype "bidirectional"))
    )
    (net (code "52") (name "/V3") (class "Default")
      (node (ref "B3") (pin "1") (pinfunction "1_1") (pintype "bidirectional"))
      (node (ref "D6") (pin "1") (pinfunction "A_1") (pintype "passive"))
      (node (ref "D6") (pin "3") (pinfunction "A_3") (pintype "passive"))
      (node (ref "R45") (pin "2") (pinfunction "2_2") (pintype "passive"))
    )
    (net (code "53") (name "/V3_ADC") (class "Default")
      (node (ref "C42") (pin "2") (pinfunction "2_2") (pintype "passive"))
      (node (ref "R45") (pin "1") (pinfunction "1_1") (pintype "passive"))
      (node (ref "R46") (pin "2") (pinfunction "2_2") (pintype "passive"))
      (node (ref "U19") (pin "26") (pinfunction "PB14_26") (pintype "bidirectional"))
    )
    (net (code "54") (name "/V4") (class "Default")
      (node (ref "B2") (pin "1") (pinfunction "1_1") (pintype "bidirectional"))
      (node (ref "Q6") (pin "2") (pinfunction "D_2") (pintype "passive"))
      (node (ref "R47") (pin "2") (pinfunction "2_2") (pintype "passive"))
    )
    (net (code "55") (name "/V4_ADC") (class "Default")
      (node (ref "C46") (pin "2") (pinfunction "2_2") (pintype "passive"))
      (node (ref "R47") (pin "1") (pinfunction "1_1") (pintype "passive"))
      (node (ref "R48") (pin "2") (pinfunction "2_2") (pintype "passive"))
      (node (ref "U19") (pin "27") (pinfunction "PB15_27") (pintype "bidirectional"))
    )
    (net (code "56") (name "/VG") (class "Default")
      (node (ref "B1") (pin "1") (pinfunction "1_1") (pintype "bidirectional"))
      (node (ref "R21") (pin "2") (pinfunction "2_2") (pintype "passive"))
      (node (ref "R51") (pin "2") (pinfunction "2_2") (pintype "passive"))
    )
    (net (code "57") (name "/VG_ADC") (class "Default")
      (node (ref "C50") (pin "2") (pinfunction "2_2") (pintype "passive"))
      (node (ref "R51") (pin "1") (pinfunction "1_1") (pintype "passive"))
      (node (ref "R52") (pin "2") (pinfunction "2_2") (pintype "passive"))
      (node (ref "U19") (pin "28") (pinfunction "PD8_28") (pintype "bidirectional"))
    )
    (net (code "58") (name "/VSYS") (class "Default")
      (node (ref "C18") (pin "2") (pinfunction "2_2") (pintype "passive"))
      (node (ref "C19") (pin "2") (pinfunction "2_2") (pintype "passive"))
      (node (ref "C20") (pin "2") (pinfunction "2_2") (pintype "passive"))
      (node (ref "C34") (pin "2") (pinfunction "2_2") (pintype "passive"))
      (node (ref "C5") (pin "2") (pinfunction "2_2") (pintype "passive"))
      (node (ref "C6") (pin "2") (pinfunction "2_2") (pintype "passive"))
      (node (ref "LD1") (pin "2") (pinfunction "A_2") (pintype "passive"))
      (node (ref "Q14") (pin "1") (pinfunction "S_1") (pintype "passive"))
      (node (ref "Q14") (pin "2") (pinfunction "S_2") (pintype "passive"))
      (node (ref "Q14") (pin "3") (pinfunction "S_3") (pintype "passive"))
      (node (ref "R22") (pin "2") (pinfunction "2_2") (pintype "passive"))
      (node (ref "R7") (pin "2") (pinfunction "2_2") (pintype "passive"))
      (node (ref "U10") (pin "1") (pinfunction "~{SHDN}_1") (pintype "input"))
      (node (ref "U10") (pin "2") (pinfunction "VIN_2") (pintype "power_in"))
      (node (ref "U14") (pin "2") (pinfunction "V+_2") (pintype "power_in"))
      (node (ref "U5") (pin "1") (pinfunction "VIN_1") (pintype "input"))
      (node (ref "U5") (pin "3") (pinfunction "ON/~{OFF}_3") (pintype "input"))
      (node (ref "U6") (pin "1") (pinfunction "VIN_1") (pintype "input"))
      (node (ref "U6") (pin "3") (pinfunction "ON/~{OFF}_3") (pintype "input"))
      (node (ref "U7") (pin "3") (pinfunction "OUT_3") (pintype "power_in"))
    )
    (net (code "59") (name "/V_ADC") (class "Default")
      (node (ref "C73") (pin "2") (pinfunction "2_2") (pintype "passive"))
      (node (ref "R57") (pin "1") (pinfunction "1_1") (pintype "passive"))
      (node (ref "U22") (pin "6") (pinfunction "IN-_6") (pintype "input"))
      (node (ref "U22") (pin "7") (pinfunction "OUT_7") (pintype "output"))
    )
    (net (code "60") (name "/V_MEAS") (class "Default")
      (node (ref "R1") (pin "1") (pinfunction "1_1") (pintype "passive"))
      (node (ref "R55") (pin "2") (pinfunction "2_2") (pintype "passive"))
      (node (ref "R62") (pin "1") (pinfunction "1_1") (pintype "passive"))
      (node (ref "U2") (pin "1") (pinfunction "OUT_1") (pintype "output"))
    )
    (net (code "61") (name "/V_OFFSET") (class "Default")
      (node (ref "R54") (pin "2") (pinfunction "2_2") (pintype "passive"))
      (node (ref "U12") (pin "6") (pinfunction "REF_6") (pintype "output"))
      (node (ref "U13") (pin "6") (pinfunction "REF_6") (pintype "output"))
      (node (ref "U16") (pin "1") (pinfunction "OUT_1") (pintype "output"))
      (node (ref "U16") (pin "4") (pinfunction "IN-_4") (pintype "input"))
    )
    (net (code "62") (name "/V_SET") (class "Default")
      (node (ref "U2") (pin "12") (pinfunction "IN+_12") (pintype "input"))
      (node (ref "U21") (pin "4") (pinfunction "VOUT_4") (pintype "output"))
    )
    (net (code "63") (name "/~{RNG_HI}") (class "Default")
      (node (ref "Q11") (pin "3") (pinfunction "D_3") (pintype "passive"))
      (node (ref "Q12") (pin "1") (pinfunction "B_1") (pintype "passive"))
      (node (ref "R18") (pin "2") (pinfunction "2_2") (pintype "passive"))
      (node (ref "U19") (pin "13") (pinfunction "PA3_13") (pintype "bidirectional"))
    )
    (net (code "64") (name "Net-(C39-Pad2)") (class "Default")
      (node (ref "C39") (pin "2") (pinfunction "2_2") (pintype "passive"))
      (node (ref "C44") (pin "2") (pinfunction "2_2") (pintype "passive"))
      (node (ref "C45") (pin "2") (pinfunction "2_2") (pintype "passive"))
      (node (ref "C47") (pin "2") (pinfunction "2_2") (pintype "passive"))
      (node (ref "L3") (pin "1") (pinfunction "1_1") (pintype "passive"))
      (node (ref "Q14") (pin "5") (pinfunction "D_5") (pintype "passive"))
      (node (ref "Q14") (pin "6") (pinfunction "D_6") (pintype "passive"))
      (node (ref "Q14") (pin "7") (pinfunction "D_7") (pintype "passive"))
      (node (ref "Q14") (pin "8") (pinfunction "D_8") (pintype "passive"))
      (node (ref "R44") (pin "2") (pinfunction "2_2") (pintype "passive"))
    )
    (net (code "65") (name "Net-(C47-Pad1)") (class "Default")
      (node (ref "C47") (pin "1") (pinfunction "1_1") (pintype "passive"))
      (node (ref "L4") (pin "1") (pinfunction "1_1") (pintype "passive"))
      (node (ref "R53") (pin "2") (pinfunction "2_2") (pintype "passive"))
      (node (ref "R56") (pin "1") (pinfunction "1_1") (pintype "passive"))
    )
    (net (code "66") (name "Net-(C72-Pad1)") (class "Default")
      (node (ref "C72") (pin "1") (pinfunction "1_1") (pintype "passive"))
      (node (ref "R61") (pin "2") (pinfunction "2_2") (pintype "passive"))
      (node (ref "R64") (pin "1") (pinfunction "1_1") (pintype "passive"))
    )
    (net (code "67") (name "Net-(C73-Pad1)") (class "Default")
      (node (ref "C73") (pin "1") (pinfunction "1_1") (pintype "passive"))
      (node (ref "R62") (pin "2") (pinfunction "2_2") (pintype "passive"))
      (node (ref "R65") (pin "1") (pinfunction "1_1") (pintype "passive"))
    )
    (net (code "68") (name "Net-(D1-C)") (class "Default")
      (node (ref "C11") (pin "2") (pinfunction "2_2") (pintype "passive"))
      (node (ref "D1") (pin "1") (pinfunction "C_1") (pintype "passive"))
      (node (ref "U7") (pin "1") (pinfunction "IN_1") (pintype "power_in"))
    )
    (net (code "69") (name "Net-(D2-A)") (class "Default")
      (node (ref "D2") (pin "2") (pinfunction "A_2") (pintype "passive"))
      (node (ref "D3") (pin "2") (pinfunction "A_2") (pintype "passive"))
      (node (ref "D4") (pin "2") (pinfunction "A_2") (pintype "passive"))
      (node (ref "D5") (pin "2") (pinfunction "A_2") (pintype "passive"))
      (node (ref "Q5") (pin "3") (pinfunction "E_3") (pintype "passive"))
    )
    (net (code "70") (name "Net-(D6A-COMC)") (class "Default")
      (node (ref "D6") (pin "2") (pinfunction "COMC_2") (pintype "passive"))
      (node (ref "Q6") (pin "3") (pinfunction "S_3") (pintype "passive"))
      (node (ref "Q7") (pin "2") (pinfunction "D_2") (pintype "passive"))
      (node (ref "R14") (pin "2") (pinfunction "2_2") (pintype "passive"))
    )
    (net (code "71") (name "Net-(D7A-COMC)") (class "Default")
      (node (ref "D7") (pin "2") (pinfunction "COMC_2") (pintype "passive"))
      (node (ref "Q7") (pin "3") (pinfunction "S_3") (pintype "passive"))
      (node (ref "Q8") (pin "2") (pinfunction "D_2") (pintype "passive"))
      (node (ref "R15") (pin "2") (pinfunction "2_2") (pintype "passive"))
    )
    (net (code "72") (name "Net-(D8A-COMC)") (class "Default")
      (node (ref "D8") (pin "2") (pinfunction "COMC_2") (pintype "passive"))
      (node (ref "Q8") (pin "3") (pinfunction "S_3") (pintype "passive"))
      (node (ref "Q9") (pin "2") (pinfunction "D_2") (pintype "passive"))
      (node (ref "R16") (pin "2") (pinfunction "2_2") (pintype "passive"))
    )
    (net (code "73") (name "Net-(J3-Pad1)") (class "Default")
      (node (ref "J3") (pin "1") (pinfunction "1_1") (pintype "bidirectional"))
      (node (ref "L4") (pin "2") (pinfunction "2_2") (pintype "passive"))
    )
    (net (code "74") (name "Net-(J3-Pad2)") (class "Default")
      (node (ref "J3") (pin "2") (pinfunction "2_2") (pintype "bidirectional"))
      (node (ref "L3") (pin "2") (pinfunction "2_2") (pintype "passive"))
    )
    (net (code "75") (name "Net-(LD1-C)") (class "Default")
      (node (ref "LD1") (pin "1") (pinfunction "C_1") (pintype "passive"))
      (node (ref "R25") (pin "2") (pinfunction "2_2") (pintype "passive"))
    )
    (net (code "76") (name "Net-(LD2-C)") (class "Default")
      (node (ref "LD2") (pin "1") (pinfunction "C_1") (pintype "passive"))
      (node (ref "R63") (pin "1") (pinfunction "1_1") (pintype "passive"))
    )
    (net (code "77") (name "Net-(Q1-C)") (class "Default")
      (node (ref "C1") (pin "2") (pinfunction "2_2") (pintype "passive"))
      (node (ref "C2") (pin "2") (pinfunction "2_2") (pintype "passive"))
      (node (ref "C4") (pin "1") (pinfunction "1_1") (pintype "passive"))
      (node (ref "Q1") (pin "3") (pinfunction "C_3") (pintype "passive"))
      (node (ref "Q2") (pin "1") (pinfunction "G_1") (pintype "passive"))
      (node (ref "Q3") (pin "3") (pinfunction "C_3") (pintype "passive"))
      (node (ref "Q4") (pin "3") (pinfunction "C_3") (pintype "passive"))
      (node (ref "R8") (pin "1") (pinfunction "1_1") (pintype "passive"))
      (node (ref "R9") (pin "1") (pinfunction "1_1") (pintype "passive"))
    )
    (net (code "78") (name "Net-(Q2-D)") (class "Default")
      (node (ref "C13") (pin "2") (pinfunction "2_2") (pintype "passive"))
      (node (ref "C14") (pin "2") (pinfunction "2_2") (pintype "passive"))
      (node (ref "Q2") (pin "3") (pinfunction "D_3") (pintype "passive"))
      (node (ref "Q5") (pin "2") (pinfunction "C_2") (pintype "passive"))
      (node (ref "Q5") (pin "4") (pinfunction "C_4") (pintype "passive"))
      (node (ref "R21") (pin "1") (pinfunction "1_1") (pintype "passive"))
      (node (ref "R3") (pin "2") (pinfunction "2_2") (pintype "passive"))
    )
    (net (code "79") (name "Net-(Q2-S)") (class "Default")
      (node (ref "Q2") (pin "2") (pinfunction "S_2") (pintype "passive"))
      (node (ref "R8") (pin "2") (pinfunction "2_2") (pintype "passive"))
    )
    (net (code "80") (name "Net-(Q3-B)") (class "Default")
      (node (ref "C4") (pin "2") (pinfunction "2_2") (pintype "passive"))
      (node (ref "Q3") (pin "1") (pinfunction "B_1") (pintype "passive"))
      (node (ref "Q4") (pin "1") (pinfunction "B_1") (pintype "passive"))
      (node (ref "R12") (pin "1") (pinfunction "1_1") (pintype "passive"))
    )
    (net (code "81") (name "Net-(Q3-E)") (class "Default")
      (node (ref "Q3") (pin "2") (pinfunction "E_2") (pintype "passive"))
      (node (ref "U2") (pin "10") (pinfunction "IN+_10") (pintype "input"))
      (node (ref "U2") (pin "14") (pinfunction "OUT_14") (pintype "output"))
    )
    (net (code "82") (name "Net-(Q4-E)") (class "Default")
      (node (ref "Q4") (pin "2") (pinfunction "E_2") (pintype "passive"))
      (node (ref "U2") (pin "7") (pinfunction "OUT_7") (pintype "output"))
      (node (ref "U2") (pin "9") (pinfunction "IN-_9") (pintype "input"))
    )
    (net (code "83") (name "Net-(Q5-B)") (class "Default")
      (node (ref "Q5") (pin "1") (pinfunction "B_1") (pintype "passive"))
      (node (ref "R9") (pin "2") (pinfunction "2_2") (pintype "passive"))
    )
    (net (code "84") (name "Net-(Q10-S)") (class "Default")
      (node (ref "Q10") (pin "2") (pinfunction "S_2") (pintype "passive"))
      (node (ref "R19") (pin "2") (pinfunction "2_2") (pintype "passive"))
    )
    (net (code "85") (name "Net-(Q11-G)") (class "Default")
      (node (ref "Q11") (pin "1") (pinfunction "G_1") (pintype "passive"))
      (node (ref "R23") (pin "1") (pinfunction "1_1") (pintype "passive"))
    )
    (net (code "86") (name "Net-(Q12-C)") (class "Default")
      (node (ref "Q12") (pin "3") (pinfunction "C_3") (pintype "passive"))
      (node (ref "Q13") (pin "4") (pinfunction "G_4") (pintype "passive"))
      (node (ref "R22") (pin "1") (pinfunction "1_1") (pintype "passive"))
    )
    (net (code "87") (name "Net-(Q13-D-Pad5)") (class "Default")
      (node (ref "Q13") (pin "5") (pinfunction "D_5") (pintype "passive"))
      (node (ref "Q13") (pin "6") (pinfunction "D_6") (pintype "passive"))
      (node (ref "Q13") (pin "7") (pinfunction "D_7") (pintype "passive"))
      (node (ref "Q13") (pin "8") (pinfunction "D_8") (pintype "passive"))
      (node (ref "R23") (pin "2") (pinfunction "2_2") (pintype "passive"))
      (node (ref "R26") (pin "2") (pinfunction "2_2") (pintype "passive"))
      (node (ref "R28") (pin "I2") (pinfunction "I2_I2") (pintype "passive"))
      (node (ref "n2") (pin "1") (pinfunction "1_1") (pintype "passive"))
    )
    (net (code "88") (name "Net-(R28-PadE1)") (class "Default")
      (node (ref "R28") (pin "E1") (pinfunction "E1_E1") (pintype "passive"))
      (node (ref "R29") (pin "1") (pinfunction "1_1") (pintype "passive"))
    )
    (net (code "89") (name "Net-(R28-PadE2)") (class "Default")
      (node (ref "R28") (pin "E2") (pinfunction "E2_E2") (pintype "passive"))
      (node (ref "R30") (pin "1") (pinfunction "1_1") (pintype "passive"))
    )
    (net (code "90") (name "Net-(R31-Pad1)") (class "Default")
      (node (ref "R31") (pin "1") (pinfunction "1_1") (pintype "passive"))
      (node (ref "n2") (pin "2") (pinfunction "2_2") (pintype "passive"))
    )
    (net (code "91") (name "Net-(R32-Pad1)") (class "Default")
      (node (ref "R32") (pin "1") (pinfunction "1_1") (pintype "passive"))
      (node (ref "n3") (pin "2") (pinfunction "2_2") (pintype "passive"))
    )
    (net (code "92") (name "Net-(R33-Pad1)") (class "Default")
      (node (ref "R33") (pin "1") (pinfunction "1_1") (pintype "passive"))
      (node (ref "U13") (pin "2") (pinfunction "RG_2") (pintype "passive"))
    )
    (net (code "93") (name "Net-(R33-Pad2)") (class "Default")
      (node (ref "R33") (pin "2") (pinfunction "2_2") (pintype "passive"))
      (node (ref "U13") (pin "3") (pinfunction "RG_3") (pintype "passive"))
    )
    (net (code "94") (name "Net-(R34-Pad1)") (class "Default")
      (node (ref "R34") (pin "1") (pinfunction "1_1") (pintype "passive"))
      (node (ref "U12") (pin "2") (pinfunction "RG_2") (pintype "passive"))
    )
    (net (code "95") (name "Net-(R34-Pad2)") (class "Default")
      (node (ref "R34") (pin "2") (pinfunction "2_2") (pintype "passive"))
      (node (ref "U12") (pin "3") (pinfunction "RG_3") (pintype "passive"))
    )
    (net (code "96") (name "Net-(U2A-IN+)") (class "Default")
      (node (ref "R49") (pin "2") (pinfunction "2_2") (pintype "passive"))
      (node (ref "R54") (pin "1") (pinfunction "1_1") (pintype "passive"))
      (node (ref "U2") (pin "3") (pinfunction "IN+_3") (pintype "input"))
    )
    (net (code "97") (name "Net-(U2A-IN-)") (class "Default")
      (node (ref "R50") (pin "2") (pinfunction "2_2") (pintype "passive"))
      (node (ref "R55") (pin "1") (pinfunction "1_1") (pintype "passive"))
      (node (ref "U2") (pin "2") (pinfunction "IN-_2") (pintype "input"))
    )
    (net (code "98") (name "Net-(U2B-IN-)") (class "Default")
      (node (ref "C2") (pin "1") (pinfunction "1_1") (pintype "passive"))
      (node (ref "R2") (pin "2") (pinfunction "2_2") (pintype "passive"))
      (node (ref "U2") (pin "6") (pinfunction "IN-_6") (pintype "input"))
    )
    (net (code "99") (name "Net-(U2D-IN-)") (class "Default")
      (node (ref "C1") (pin "1") (pinfunction "1_1") (pintype "passive"))
      (node (ref "R1") (pin "2") (pinfunction "2_2") (pintype "passive"))
      (node (ref "U2") (pin "13") (pinfunction "IN-_13") (pintype "input"))
    )
    (net (code "100") (name "Net-(U5-BYP)") (class "Default")
      (node (ref "C8") (pin "2") (pinfunction "2_2") (pintype "passive"))
      (node (ref "U5") (pin "4") (pinfunction "BYP_4") (pintype "passive"))
    )
    (net (code "101") (name "Net-(U6-BYP)") (class "Default")
      (node (ref "C9") (pin "2") (pinfunction "2_2") (pintype "passive"))
      (node (ref "U6") (pin "4") (pinfunction "BYP_4") (pintype "passive"))
    )
    (net (code "102") (name "Net-(U8-C+)") (class "Default")
      (node (ref "C12") (pin "1") (pinfunction "1_1") (pintype "passive"))
      (node (ref "U8") (pin "8") (pinfunction "C+_8") (pintype "output"))
    )
    (net (code "103") (name "Net-(U8-C-)") (class "Default")
      (node (ref "C12") (pin "2") (pinfunction "2_2") (pintype "passive"))
      (node (ref "U8") (pin "7") (pinfunction "C-_7") (pintype "output"))
    )
    (net (code "104") (name "Net-(U8-CPOUT)") (class "Default")
      (node (ref "C21") (pin "1") (pinfunction "1_1") (pintype "passive"))
      (node (ref "U8") (pin "3") (pinfunction "CPOUT_3") (pintype "output"))
    )
    (net (code "105") (name "Net-(U8-EN)") (class "Default")
      (node (ref "C10") (pin "1") (pinfunction "1_1") (pintype "passive"))
      (node (ref "L1") (pin "2") (pinfunction "2_2") (pintype "passive"))
      (node (ref "U8") (pin "1") (pinfunction "VIN_1") (pintype "power_in"))
      (node (ref "U8") (pin "6") (pinfunction "EN_6") (pintype "input"))
    )
    (net (code "106") (name "Net-(U8-VFB)") (class "Default")
      (node (ref "R24") (pin "2") (pinfunction "2_2") (pintype "passive"))
      (node (ref "R27") (pin "2") (pinfunction "2_2") (pintype "passive"))
      (node (ref "U8") (pin "5") (pinfunction "VFB_5") (pintype "input"))
    )
    (net (code "107") (name "Net-(U8-VOUT)") (class "Default")
      (node (ref "C23") (pin "1") (pinfunction "1_1") (pintype "passive"))
      (node (ref "L2") (pin "1") (pinfunction "1_1") (pintype "passive"))
      (node (ref "R27") (pin "1") (pinfunction "1_1") (pintype "passive"))
      (node (ref "U8") (pin "4") (pinfunction "VOUT_4") (pintype "output"))
    )
    (net (code "108") (name "Net-(U12-+IN)") (class "Default")
      (node (ref "R31") (pin "2") (pinfunction "2_2") (pintype "passive"))
      (node (ref "U12") (pin "4") (pinfunction "+IN_4") (pintype "input"))
    )
    (net (code "109") (name "Net-(U12--IN)") (class "Default")
      (node (ref "R32") (pin "2") (pinfunction "2_2") (pintype "passive"))
      (node (ref "U12") (pin "1") (pinfunction "-IN_1") (pintype "input"))
    )
    (net (code "110") (name "Net-(U13-+IN)") (class "Default")
      (node (ref "R29") (pin "2") (pinfunction "2_2") (pintype "passive"))
      (node (ref "U13") (pin "4") (pinfunction "+IN_4") (pintype "input"))
    )
    (net (code "111") (name "Net-(U13--IN)") (class "Default")
      (node (ref "R30") (pin "2") (pinfunction "2_2") (pintype "passive"))
      (node (ref "U13") (pin "1") (pinfunction "-IN_1") (pintype "input"))
    )
    (net (code "112") (name "Net-(U14-IN+)") (class "Default")
      (node (ref "C39") (pin "1") (pinfunction "1_1") (pintype "passive"))
      (node (ref "R42") (pin "2") (pinfunction "2_2") (pintype "passive"))
      (node (ref "R44") (pin "1") (pinfunction "1_1") (pintype "passive"))
      (node (ref "U14") (pin "3") (pinfunction "IN+_3") (pintype "input"))
    )
    (net (code "113") (name "Net-(U14-IN-)") (class "Default")
      (node (ref "C35") (pin "2") (pinfunction "2_2") (pintype "passive"))
      (node (ref "R37") (pin "2") (pinfunction "2_2") (pintype "passive"))
      (node (ref "U14") (pin "4") (pinfunction "IN-_4") (pintype "input"))
    )
    (net (code "114") (name "Net-(U14-OUT)") (class "Default")
      (node (ref "Q14") (pin "4") (pinfunction "S_4") (pintype "passive"))
      (node (ref "U14") (pin "1") (pinfunction "OUT_1") (pintype "output"))
    )
    (net (code "115") (name "Net-(U15-IN+)") (class "Default")
      (node (ref "R43") (pin "2") (pinfunction "2_2") (pintype "passive"))
      (node (ref "U15") (pin "3") (pinfunction "IN+_3") (pintype "input"))
    )
    (net (code "116") (name "Net-(U15-IN-)") (class "Default")
      (node (ref "R50") (pin "1") (pinfunction "1_1") (pintype "passive"))
      (node (ref "U15") (pin "1") (pinfunction "OUT_1") (pintype "output"))
      (node (ref "U15") (pin "4") (pinfunction "IN-_4") (pintype "input"))
    )
    (net (code "117") (name "Net-(U16-IN+)") (class "Default")
      (node (ref "C37") (pin "2") (pinfunction "2_2") (pintype "passive"))
      (node (ref "R40") (pin "1") (pinfunction "1_1") (pintype "passive"))
      (node (ref "R41") (pin "2") (pinfunction "2_2") (pintype "passive"))
      (node (ref "U16") (pin "3") (pinfunction "IN+_3") (pintype "input"))
    )
    (net (code "118") (name "Net-(U18-COM)") (class "Default")
      (node (ref "R61") (pin "1") (pinfunction "1_1") (pintype "passive"))
      (node (ref "U18") (pin "4") (pinfunction "COM_4") (pintype "bidirectional"))
    )
    (net (code "119") (name "Net-(U20-INA+)") (class "Default")
      (node (ref "C60") (pin "2") (pinfunction "2_2") (pintype "passive"))
      (node (ref "R57") (pin "2") (pinfunction "2_2") (pintype "passive"))
      (node (ref "U20") (pin "8") (pinfunction "INA+_8") (pintype "input"))
    )
    (net (code "120") (name "Net-(U20-INA-)") (class "Default")
      (node (ref "C60") (pin "1") (pinfunction "1_1") (pintype "passive"))
      (node (ref "R58") (pin "2") (pinfunction "2_2") (pintype "passive"))
      (node (ref "U20") (pin "7") (pinfunction "INA-_7") (pintype "input"))
    )
    (net (code "121") (name "Net-(U20-INB+)") (class "Default")
      (node (ref "C61") (pin "2") (pinfunction "2_2") (pintype "passive"))
      (node (ref "R59") (pin "2") (pinfunction "2_2") (pintype "passive"))
      (node (ref "U20") (pin "6") (pinfunction "INB+_6") (pintype "input"))
    )
    (net (code "122") (name "Net-(U20-INB-)") (class "Default")
      (node (ref "C61") (pin "1") (pinfunction "1_1") (pintype "passive"))
      (node (ref "R60") (pin "2") (pinfunction "2_2") (pintype "passive"))
      (node (ref "U20") (pin "5") (pinfunction "INB-_5") (pintype "input"))
    )
    (net (code "123") (name "Net-(U20-REFCAP)") (class "Default")
      (node (ref "C79") (pin "2") (pinfunction "2_2") (pintype "passive"))
      (node (ref "U20") (pin "9") (pinfunction "REFCAP_9") (pintype "power_in"))
    )
    (net (code "124") (name "Net-(U20-REGCAP)") (class "Default")
      (node (ref "C78") (pin "2") (pinfunction "2_2") (pintype "passive"))
      (node (ref "U20") (pin "3") (pinfunction "REGCAP_3") (pintype "power_in"))
    )
    (net (code "125") (name "Net-(U22A-IN+)") (class "Default")
      (node (ref "C69") (pin "2") (pinfunction "2_2") (pintype "passive"))
      (node (ref "R64") (pin "2") (pinfunction "2_2") (pintype "passive"))
      (node (ref "U22") (pin "3") (pinfunction "IN+_3") (pintype "input"))
    )
    (net (code "126") (name "Net-(U22B-IN+)") (class "Default")
      (node (ref "C70") (pin "2") (pinfunction "2_2") (pintype "passive"))
      (node (ref "R65") (pin "2") (pinfunction "2_2") (pintype "passive"))
      (node (ref "U22") (pin "5") (pinfunction "IN+_5") (pintype "input"))
    )
    (net (code "127") (name "unconnected-(MH1-Pad1)") (class "Default")
      (node (ref "MH1") (pin "1") (pinfunction "1_1") (pintype "bidirectional"))
    )
    (net (code "128") (name "unconnected-(MH2-Pad1)") (class "Default")
      (node (ref "MH2") (pin "1") (pinfunction "1_1") (pintype "bidirectional"))
    )
    (net (code "129") (name "unconnected-(MH3-Pad1)") (class "Default")
      (node (ref "MH3") (pin "1") (pinfunction "1_1") (pintype "bidirectional"))
    )
    (net (code "130") (name "unconnected-(MH4-Pad1)") (class "Default")
      (node (ref "MH4") (pin "1") (pinfunction "1_1") (pintype "bidirectional"))
    )
    (net (code "131") (name "unconnected-(U3-I{slash}O1-Pad1)") (class "Default")
      (node (ref "U3") (pin "1") (pinfunction "I/O1_1") (pintype "bidirectional"))
    )
    (net (code "132") (name "unconnected-(U3-I{slash}O2-Pad3)") (class "Default")
      (node (ref "U3") (pin "3") (pinfunction "I/O2_3") (pintype "bidirectional"))
    )
    (net (code "133") (name "unconnected-(U3-VP-Pad5)") (class "Default")
      (node (ref "U3") (pin "5") (pinfunction "VP_5") (pintype "power_in"))
    )
    (net (code "134") (name "unconnected-(U19-PA5-Pad15)") (class "Default")
      (node (ref "U19") (pin "15") (pinfunction "PA5_15") (pintype "bidirectional"))
    )
    (net (code "135") (name "unconnected-(U19-PA6-Pad16)") (class "Default")
      (node (ref "U19") (pin "16") (pinfunction "PA6_16") (pintype "bidirectional"))
    )
    (net (code "136") (name "unconnected-(U19-PA8-Pad29)") (class "Default")
      (node (ref "U19") (pin "29") (pinfunction "PA8_29") (pintype "bidirectional"))
    )
    (net (code "137") (name "unconnected-(U19-PA11-Pad32)") (class "Default")
      (node (ref "U19") (pin "32") (pinfunction "PA11_32") (pintype "bidirectional"))
    )
    (net (code "138") (name "unconnected-(U19-PC13-Pad2)") (class "Default")
      (node (ref "U19") (pin "2") (pinfunction "PC13_2") (pintype "bidirectional"))
    )
    (net (code "139") (name "unconnected-(U19-PC14-Pad3)") (class "Default")
      (node (ref "U19") (pin "3") (pinfunction "PC14_3") (pintype "bidirectional"))
    )
    (net (code "140") (name "unconnected-(U19-PC15-Pad4)") (class "Default")
      (node (ref "U19") (pin "4") (pinfunction "PC15_4") (pintype "bidirectional"))
    )
    (net (code "141") (name "unconnected-(U20-SDOB{slash}~{ALERT}-Pad14)") (class "Default")
      (node (ref "U20") (pin "14") (pinfunction "SDOB/~{ALERT}_14") (pintype "output"))
    )
  )
)
